# FPGA.net
KiCad netlist of a schematic drawn in Altium Designer
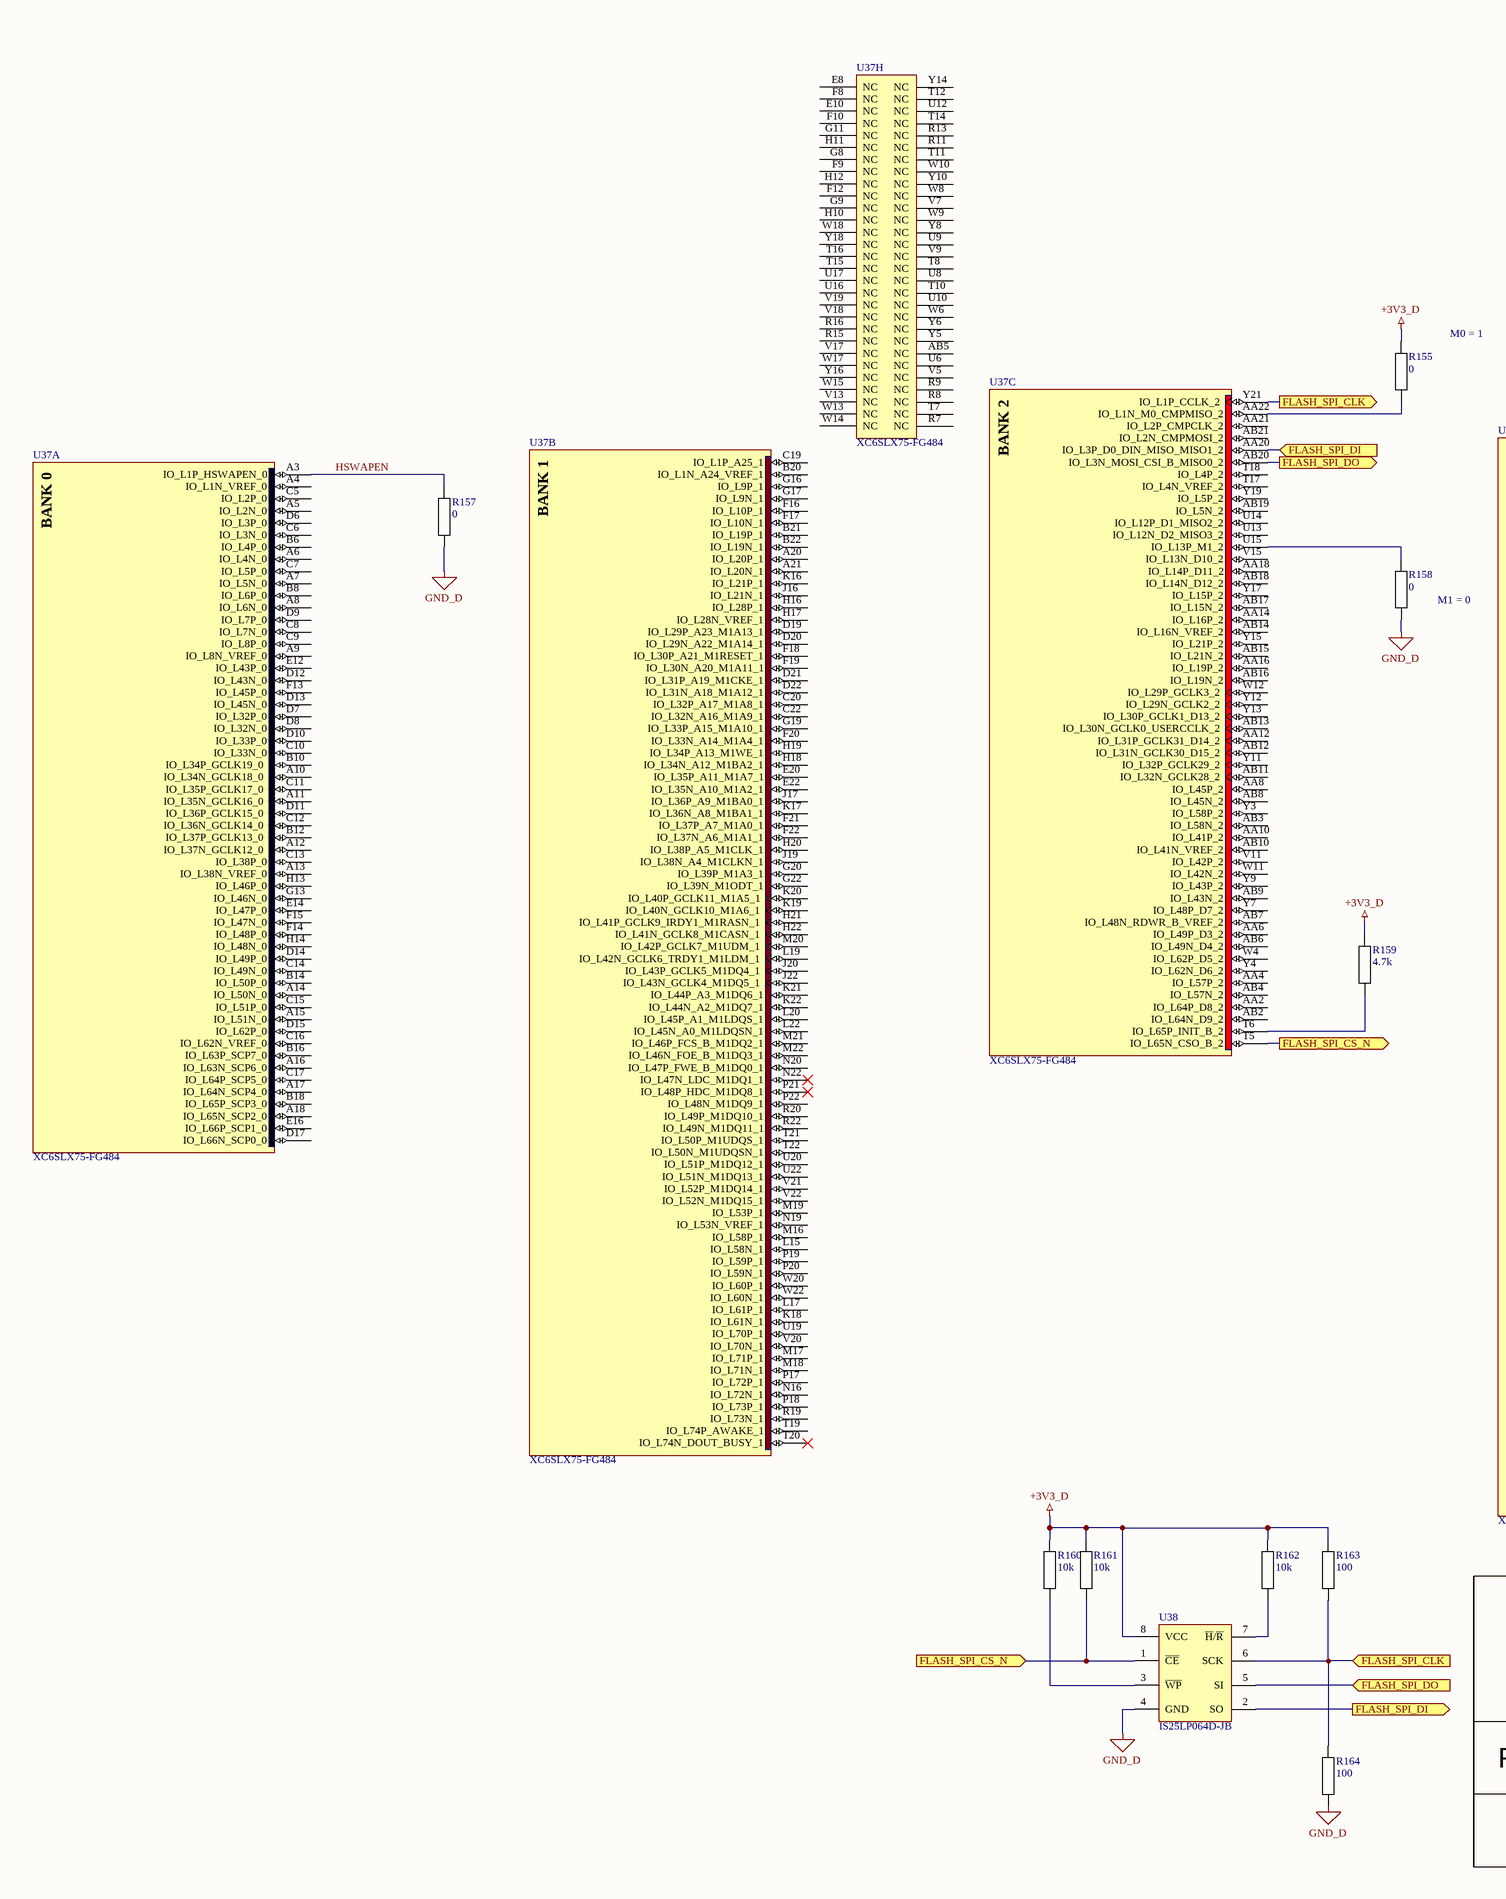
[diagram p0: FPGA.SchDoc, left]
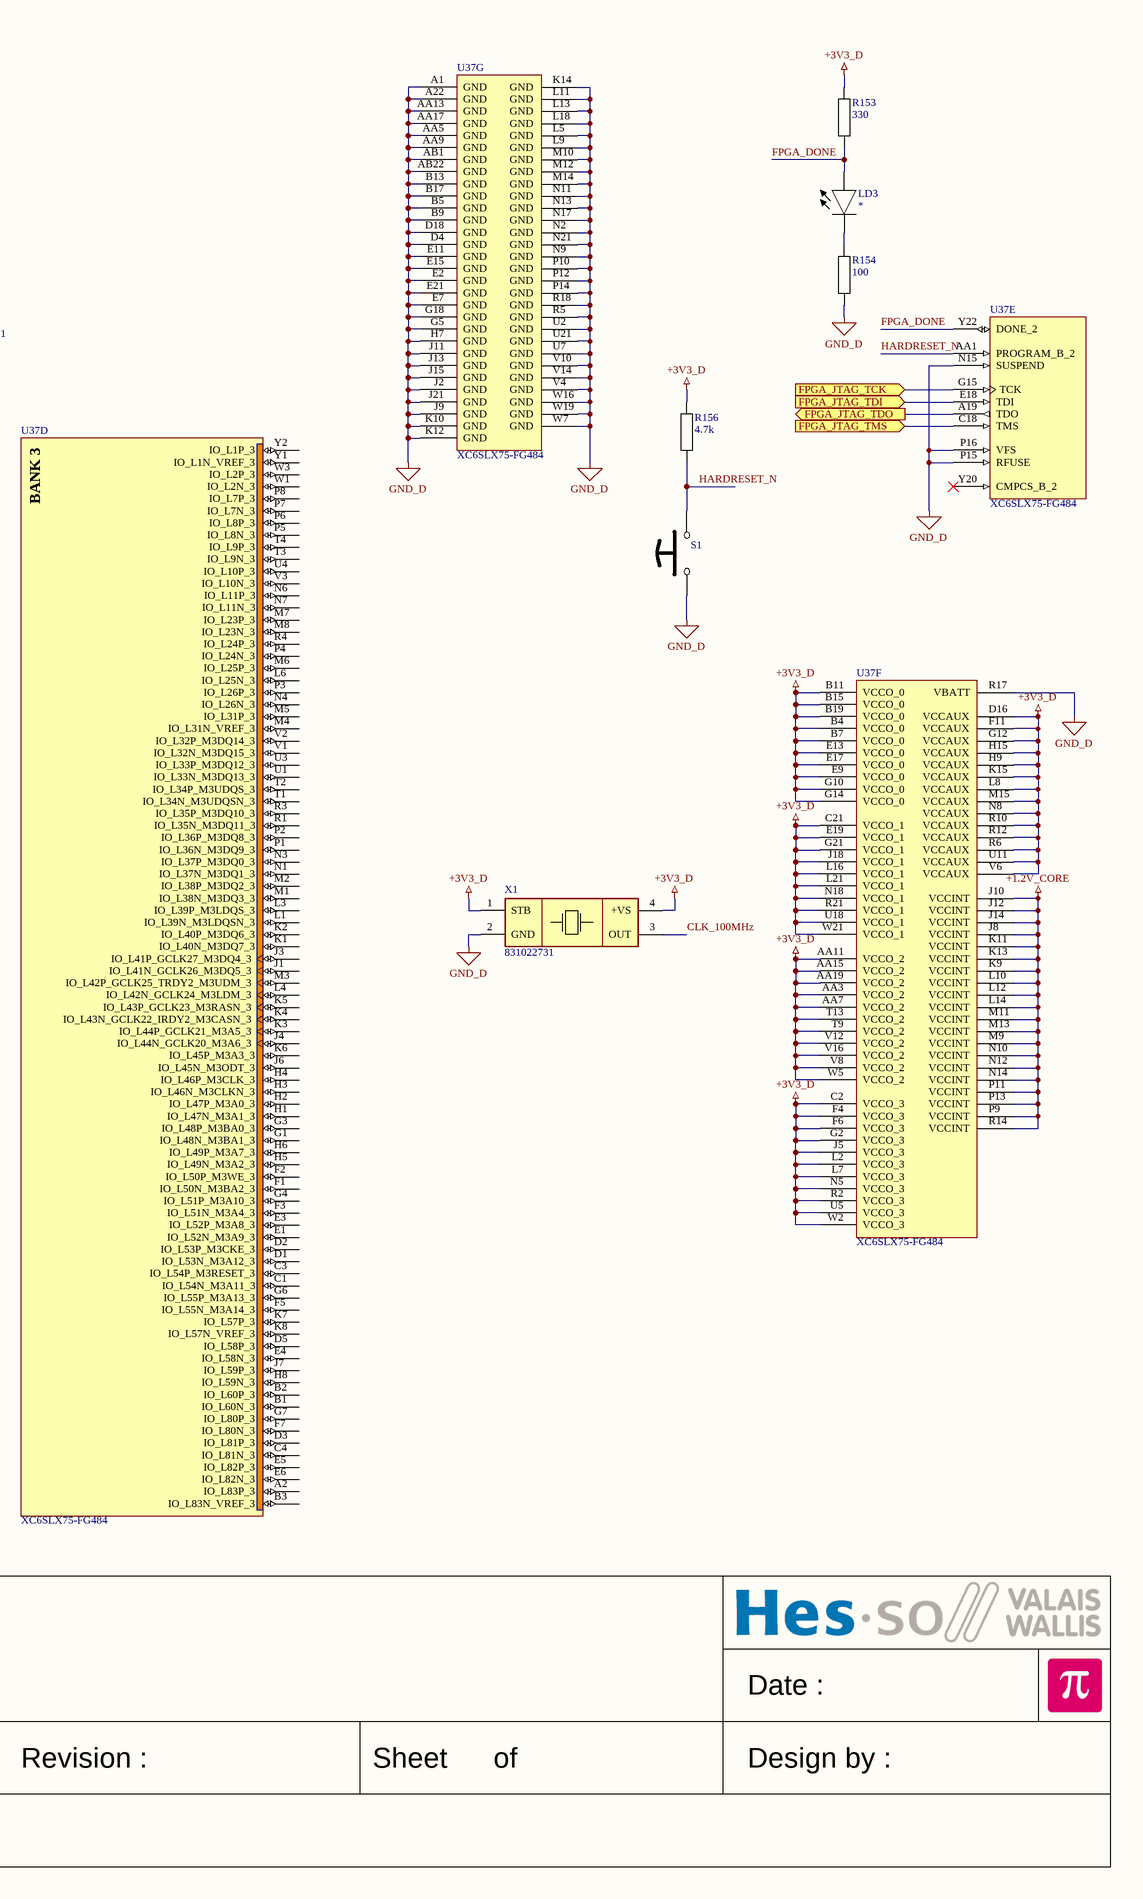
[diagram p1: FPGA.SchDoc, right]

(export (version "E")
  (design (tool "Eeschema 10.0.6"))
  (components
    (comp (ref "LD3")
      (value "*")
      (footprint "LED 1608 REFLOW")
      (description "LED generic")
      (libsource (lib "Diode") (part "LED"))
    )
    (comp (ref "R153")
      (value "330")
      (footprint "RESISTOR 2012 REFLOW")
      (description "Resistor 1% 50V 125mW 2012(0805)")
      (libsource (lib "Resistor") (part "Resistor"))
    )
    (comp (ref "R154")
      (value "100")
      (footprint "RESISTOR 2012 REFLOW")
      (description "Resistor 1% 50V 125mW 2012(0805)")
      (libsource (lib "Resistor") (part "Resistor"))
    )
    (comp (ref "R155")
      (value "0")
      (footprint "RESISTOR 2012 REFLOW")
      (description "Resistor 1% 50V 125mW 2012(0805)")
      (libsource (lib "Resistor") (part "Resistor"))
    )
    (comp (ref "R156")
      (value "4.7k")
      (footprint "RESISTOR 2012 REFLOW")
      (description "Resistor 1% 50V 125mW 2012(0805)")
      (libsource (lib "Resistor") (part "Resistor"))
    )
    (comp (ref "R157")
      (value "0")
      (footprint "RESISTOR 2012 REFLOW")
      (description "Resistor 1% 50V 125mW 2012(0805)")
      (libsource (lib "Resistor") (part "Resistor"))
    )
    (comp (ref "R158")
      (value "0")
      (footprint "RESISTOR 2012 REFLOW")
      (description "Resistor 1% 50V 125mW 2012(0805)")
      (libsource (lib "Resistor") (part "Resistor"))
    )
    (comp (ref "R159")
      (value "4.7k")
      (footprint "RESISTOR 2012 REFLOW")
      (description "Resistor 1% 50V 125mW 2012(0805)")
      (libsource (lib "Resistor") (part "Resistor"))
    )
    (comp (ref "R160")
      (value "10k")
      (footprint "RESISTOR 1608 REFLOW")
      (description "Resistor 1% 50V 100mW 1608(0603)")
      (libsource (lib "Resistor") (part "Resistor"))
    )
    (comp (ref "R161")
      (value "10k")
      (footprint "RESISTOR 1608 REFLOW")
      (description "Resistor 1% 50V 100mW 1608(0603)")
      (libsource (lib "Resistor") (part "Resistor"))
    )
    (comp (ref "R162")
      (value "10k")
      (footprint "RESISTOR 1608 REFLOW")
      (description "Resistor 1% 50V 100mW 1608(0603)")
      (libsource (lib "Resistor") (part "Resistor"))
    )
    (comp (ref "R163")
      (value "100")
      (footprint "RESISTOR 1608 REFLOW")
      (description "Resistor 1% 50V 100mW 1608(0603)")
      (libsource (lib "Resistor") (part "Resistor"))
    )
    (comp (ref "R164")
      (value "100")
      (footprint "RESISTOR 1608 REFLOW")
      (description "Resistor 1% 50V 100mW 1608(0603)")
      (libsource (lib "Resistor") (part "Resistor"))
    )
    (comp (ref "S1")
      (value "*")
      (footprint "Push Button C2.5X3.0 OMRON B3U-1000P(M)-B")
      (description "Push Button, 2 pins")
      (libsource (lib "Button") (part "Push Button 2Pins"))
    )
    (comp (ref "U37")
      (value "XC6SLX75-FG484")
      (footprint "BGA484 P1.0 C23X23 H2.2")
      (description "Spartan-6 LXT 1.2V FPGA, 268 User I/Os, 484-Ball Fine-Pitch BGA (1.0mm Pitch)")
      (libsource (lib "Processor") (part "XC6SLX75-FG484"))
    )
    (comp (ref "U38")
      (value "IS25LP064D-JB")
      (footprint "SO8 P1.27 C4.0X5.0 H1.75")
      (description "64Mb Serial Flash Memory")
      (libsource (lib "Memory") (part "IS25LP064D-JB"))
    )
    (comp (ref "X1")
      (value "831022731")
      (footprint "Oscillator C5.2x7.2 IQD LFSPXO")
      (description "Oscillator C5.2x7.2 IQD LFSPXO")
      (libsource (lib "Oscillator") (part "Oscillator C5.2x7.2 IQD LFSPXO"))
    )
  )
  (nets
    (net (code "1") (name "+1.2V_CORE") (class "Default")
      (node (ref "U37") (pin "J10") (pinfunction "VCCINT_J10") (pintype "power_in"))
      (node (ref "U37") (pin "J12") (pinfunction "VCCINT_J12") (pintype "power_in"))
      (node (ref "U37") (pin "J14") (pinfunction "VCCINT_J14") (pintype "power_in"))
      (node (ref "U37") (pin "J8") (pinfunction "VCCINT_J8") (pintype "power_in"))
      (node (ref "U37") (pin "K11") (pinfunction "VCCINT_K11") (pintype "power_in"))
      (node (ref "U37") (pin "K13") (pinfunction "VCCINT_K13") (pintype "power_in"))
      (node (ref "U37") (pin "K9") (pinfunction "VCCINT_K9") (pintype "power_in"))
      (node (ref "U37") (pin "L10") (pinfunction "VCCINT_L10") (pintype "power_in"))
      (node (ref "U37") (pin "L12") (pinfunction "VCCINT_L12") (pintype "power_in"))
      (node (ref "U37") (pin "L14") (pinfunction "VCCINT_L14") (pintype "power_in"))
      (node (ref "U37") (pin "M11") (pinfunction "VCCINT_M11") (pintype "power_in"))
      (node (ref "U37") (pin "M13") (pinfunction "VCCINT_M13") (pintype "power_in"))
      (node (ref "U37") (pin "M9") (pinfunction "VCCINT_M9") (pintype "power_in"))
      (node (ref "U37") (pin "N10") (pinfunction "VCCINT_N10") (pintype "power_in"))
      (node (ref "U37") (pin "N12") (pinfunction "VCCINT_N12") (pintype "power_in"))
      (node (ref "U37") (pin "N14") (pinfunction "VCCINT_N14") (pintype "power_in"))
      (node (ref "U37") (pin "P11") (pinfunction "VCCINT_P11") (pintype "power_in"))
      (node (ref "U37") (pin "P13") (pinfunction "VCCINT_P13") (pintype "power_in"))
      (node (ref "U37") (pin "P9") (pinfunction "VCCINT_P9") (pintype "power_in"))
      (node (ref "U37") (pin "R14") (pinfunction "VCCINT_R14") (pintype "power_in"))
    )
    (net (code "2") (name "+3V3_D") (class "Default")
      (node (ref "R153") (pin "2") (pinfunction "2_2") (pintype "passive"))
      (node (ref "R155") (pin "2") (pinfunction "2_2") (pintype "passive"))
      (node (ref "R156") (pin "2") (pinfunction "2_2") (pintype "passive"))
      (node (ref "R159") (pin "2") (pinfunction "2_2") (pintype "passive"))
      (node (ref "R160") (pin "2") (pinfunction "2_2") (pintype "passive"))
      (node (ref "R161") (pin "2") (pinfunction "2_2") (pintype "passive"))
      (node (ref "R162") (pin "2") (pinfunction "2_2") (pintype "passive"))
      (node (ref "R163") (pin "2") (pinfunction "2_2") (pintype "passive"))
      (node (ref "U37") (pin "AA11") (pinfunction "VCCO_2_AA11") (pintype "power_in"))
      (node (ref "U37") (pin "AA15") (pinfunction "VCCO_2_AA15") (pintype "power_in"))
      (node (ref "U37") (pin "AA19") (pinfunction "VCCO_2_AA19") (pintype "power_in"))
      (node (ref "U37") (pin "AA3") (pinfunction "VCCO_2_AA3") (pintype "power_in"))
      (node (ref "U37") (pin "AA7") (pinfunction "VCCO_2_AA7") (pintype "power_in"))
      (node (ref "U37") (pin "B11") (pinfunction "VCCO_0_B11") (pintype "power_in"))
      (node (ref "U37") (pin "B15") (pinfunction "VCCO_0_B15") (pintype "power_in"))
      (node (ref "U37") (pin "B19") (pinfunction "VCCO_0_B19") (pintype "power_in"))
      (node (ref "U37") (pin "B4") (pinfunction "VCCO_0_B4") (pintype "power_in"))
      (node (ref "U37") (pin "B7") (pinfunction "VCCO_0_B7") (pintype "power_in"))
      (node (ref "U37") (pin "C2") (pinfunction "VCCO_3_C2") (pintype "power_in"))
      (node (ref "U37") (pin "C21") (pinfunction "VCCO_1_C21") (pintype "power_in"))
      (node (ref "U37") (pin "D16") (pinfunction "VCCAUX_D16") (pintype "power_in"))
      (node (ref "U37") (pin "E13") (pinfunction "VCCO_0_E13") (pintype "power_in"))
      (node (ref "U37") (pin "E17") (pinfunction "VCCO_0_E17") (pintype "power_in"))
      (node (ref "U37") (pin "E19") (pinfunction "VCCO_1_E19") (pintype "power_in"))
      (node (ref "U37") (pin "E9") (pinfunction "VCCO_0_E9") (pintype "power_in"))
      (node (ref "U37") (pin "F11") (pinfunction "VCCAUX_F11") (pintype "power_in"))
      (node (ref "U37") (pin "F4") (pinfunction "VCCO_3_F4") (pintype "power_in"))
      (node (ref "U37") (pin "F6") (pinfunction "VCCO_3_F6") (pintype "power_in"))
      (node (ref "U37") (pin "G10") (pinfunction "VCCO_0_G10") (pintype "power_in"))
      (node (ref "U37") (pin "G12") (pinfunction "VCCAUX_G12") (pintype "power_in"))
      (node (ref "U37") (pin "G14") (pinfunction "VCCO_0_G14") (pintype "power_in"))
      (node (ref "U37") (pin "G2") (pinfunction "VCCO_3_G2") (pintype "power_in"))
      (node (ref "U37") (pin "G21") (pinfunction "VCCO_1_G21") (pintype "power_in"))
      (node (ref "U37") (pin "H15") (pinfunction "VCCAUX_H15") (pintype "power_in"))
      (node (ref "U37") (pin "H9") (pinfunction "VCCAUX_H9") (pintype "power_in"))
      (node (ref "U37") (pin "J18") (pinfunction "VCCO_1_J18") (pintype "power_in"))
      (node (ref "U37") (pin "J5") (pinfunction "VCCO_3_J5") (pintype "power_in"))
      (node (ref "U37") (pin "K15") (pinfunction "VCCAUX_K15") (pintype "power_in"))
      (node (ref "U37") (pin "L16") (pinfunction "VCCO_1_L16") (pintype "power_in"))
      (node (ref "U37") (pin "L2") (pinfunction "VCCO_3_L2") (pintype "power_in"))
      (node (ref "U37") (pin "L21") (pinfunction "VCCO_1_L21") (pintype "power_in"))
      (node (ref "U37") (pin "L7") (pinfunction "VCCO_3_L7") (pintype "power_in"))
      (node (ref "U37") (pin "L8") (pinfunction "VCCAUX_L8") (pintype "power_in"))
      (node (ref "U37") (pin "M15") (pinfunction "VCCAUX_M15") (pintype "power_in"))
      (node (ref "U37") (pin "N18") (pinfunction "VCCO_1_N18") (pintype "power_in"))
      (node (ref "U37") (pin "N5") (pinfunction "VCCO_3_N5") (pintype "power_in"))
      (node (ref "U37") (pin "N8") (pinfunction "VCCAUX_N8") (pintype "power_in"))
      (node (ref "U37") (pin "R10") (pinfunction "VCCAUX_R10") (pintype "power_in"))
      (node (ref "U37") (pin "R12") (pinfunction "VCCAUX_R12") (pintype "power_in"))
      (node (ref "U37") (pin "R2") (pinfunction "VCCO_3_R2") (pintype "power_in"))
      (node (ref "U37") (pin "R21") (pinfunction "VCCO_1_R21") (pintype "power_in"))
      (node (ref "U37") (pin "R6") (pinfunction "VCCAUX_R6") (pintype "power_in"))
      (node (ref "U37") (pin "T13") (pinfunction "VCCO_2_T13") (pintype "power_in"))
      (node (ref "U37") (pin "T9") (pinfunction "VCCO_2_T9") (pintype "power_in"))
      (node (ref "U37") (pin "U11") (pinfunction "VCCAUX_U11") (pintype "power_in"))
      (node (ref "U37") (pin "U18") (pinfunction "VCCO_1_U18") (pintype "power_in"))
      (node (ref "U37") (pin "U5") (pinfunction "VCCO_3_U5") (pintype "power_in"))
      (node (ref "U37") (pin "V12") (pinfunction "VCCO_2_V12") (pintype "power_in"))
      (node (ref "U37") (pin "V16") (pinfunction "VCCO_2_V16") (pintype "power_in"))
      (node (ref "U37") (pin "V6") (pinfunction "VCCAUX_V6") (pintype "power_in"))
      (node (ref "U37") (pin "V8") (pinfunction "VCCO_2_V8") (pintype "power_in"))
      (node (ref "U37") (pin "W2") (pinfunction "VCCO_3_W2") (pintype "power_in"))
      (node (ref "U37") (pin "W21") (pinfunction "VCCO_1_W21") (pintype "power_in"))
      (node (ref "U37") (pin "W5") (pinfunction "VCCO_2_W5") (pintype "power_in"))
      (node (ref "U38") (pin "8") (pinfunction "VCC_8") (pintype "power_in"))
      (node (ref "X1") (pin "1") (pinfunction "STB_1") (pintype "passive"))
      (node (ref "X1") (pin "4") (pinfunction "+VS_4") (pintype "passive"))
    )
    (net (code "3") (name "/CLK_100MHz") (class "Default")
      (node (ref "X1") (pin "3") (pinfunction "OUT_3") (pintype "passive"))
    )
    (net (code "4") (name "/FLASH_SPI_CLK") (class "Default")
      (node (ref "R163") (pin "1") (pinfunction "1_1") (pintype "passive"))
      (node (ref "R164") (pin "2") (pinfunction "2_2") (pintype "passive"))
      (node (ref "U37") (pin "Y21") (pinfunction "IO_L1P_CCLK_2_Y21") (pintype "bidirectional"))
      (node (ref "U38") (pin "6") (pinfunction "SCK_6") (pintype "passive"))
    )
    (net (code "5") (name "/FLASH_SPI_CS_N") (class "Default")
      (node (ref "R161") (pin "1") (pinfunction "1_1") (pintype "passive"))
      (node (ref "U37") (pin "T5") (pinfunction "IO_L65N_CSO_B_2_T5") (pintype "bidirectional"))
      (node (ref "U38") (pin "1") (pinfunction "~{CE}_1") (pintype "passive"))
    )
    (net (code "6") (name "/FLASH_SPI_DI") (class "Default")
      (node (ref "U37") (pin "AA20") (pinfunction "IO_L3P_D0_DIN_MISO_MISO1_2_AA20") (pintype "bidirectional"))
      (node (ref "U38") (pin "2") (pinfunction "SO_2") (pintype "passive"))
    )
    (net (code "7") (name "/FLASH_SPI_DO") (class "Default")
      (node (ref "U37") (pin "AB20") (pinfunction "IO_L3N_MOSI_CSI_B_MISO0_2_AB20") (pintype "bidirectional"))
      (node (ref "U38") (pin "5") (pinfunction "SI_5") (pintype "passive"))
    )
    (net (code "8") (name "/FPGA_DONE") (class "Default")
      (node (ref "LD3") (pin "2") (pinfunction "A_2") (pintype "passive"))
      (node (ref "R153") (pin "1") (pinfunction "1_1") (pintype "passive"))
      (node (ref "U37") (pin "Y22") (pinfunction "DONE_2_Y22") (pintype "bidirectional"))
    )
    (net (code "9") (name "/FPGA_JTAG_TCK") (class "Default")
      (node (ref "U37") (pin "G15") (pinfunction "TCK_G15") (pintype "input"))
    )
    (net (code "10") (name "/FPGA_JTAG_TDI") (class "Default")
      (node (ref "U37") (pin "E18") (pinfunction "TDI_E18") (pintype "input"))
    )
    (net (code "11") (name "/FPGA_JTAG_TDO") (class "Default")
      (node (ref "U37") (pin "A19") (pinfunction "TDO_A19") (pintype "output"))
    )
    (net (code "12") (name "/FPGA_JTAG_TMS") (class "Default")
      (node (ref "U37") (pin "C18") (pinfunction "TMS_C18") (pintype "input"))
    )
    (net (code "13") (name "/HARDRESET_N") (class "Default")
      (node (ref "R156") (pin "1") (pinfunction "1_1") (pintype "passive"))
      (node (ref "S1") (pin "2") (pinfunction "2_2") (pintype "passive"))
      (node (ref "U37") (pin "AA1") (pinfunction "PROGRAM_B_2_AA1") (pintype "input"))
    )
    (net (code "14") (name "/HSWAPEN") (class "Default")
      (node (ref "R157") (pin "2") (pinfunction "2_2") (pintype "passive"))
      (node (ref "U37") (pin "A3") (pinfunction "IO_L1P_HSWAPEN_0_A3") (pintype "bidirectional"))
    )
    (net (code "15") (name "GND_D") (class "Default")
      (node (ref "R154") (pin "1") (pinfunction "1_1") (pintype "passive"))
      (node (ref "R157") (pin "1") (pinfunction "1_1") (pintype "passive"))
      (node (ref "R158") (pin "1") (pinfunction "1_1") (pintype "passive"))
      (node (ref "R164") (pin "1") (pinfunction "1_1") (pintype "passive"))
      (node (ref "S1") (pin "1") (pinfunction "1_1") (pintype "passive"))
      (node (ref "U37") (pin "A1") (pinfunction "GND_A1") (pintype "power_in"))
      (node (ref "U37") (pin "A22") (pinfunction "GND_A22") (pintype "power_in"))
      (node (ref "U37") (pin "AA13") (pinfunction "GND_AA13") (pintype "power_in"))
      (node (ref "U37") (pin "AA17") (pinfunction "GND_AA17") (pintype "power_in"))
      (node (ref "U37") (pin "AA5") (pinfunction "GND_AA5") (pintype "power_in"))
      (node (ref "U37") (pin "AA9") (pinfunction "GND_AA9") (pintype "power_in"))
      (node (ref "U37") (pin "AB1") (pinfunction "GND_AB1") (pintype "power_in"))
      (node (ref "U37") (pin "AB22") (pinfunction "GND_AB22") (pintype "power_in"))
      (node (ref "U37") (pin "B13") (pinfunction "GND_B13") (pintype "power_in"))
      (node (ref "U37") (pin "B17") (pinfunction "GND_B17") (pintype "power_in"))
      (node (ref "U37") (pin "B5") (pinfunction "GND_B5") (pintype "power_in"))
      (node (ref "U37") (pin "B9") (pinfunction "GND_B9") (pintype "power_in"))
      (node (ref "U37") (pin "D18") (pinfunction "GND_D18") (pintype "power_in"))
      (node (ref "U37") (pin "D4") (pinfunction "GND_D4") (pintype "power_in"))
      (node (ref "U37") (pin "E11") (pinfunction "GND_E11") (pintype "power_in"))
      (node (ref "U37") (pin "E15") (pinfunction "GND_E15") (pintype "power_in"))
      (node (ref "U37") (pin "E2") (pinfunction "GND_E2") (pintype "power_in"))
      (node (ref "U37") (pin "E21") (pinfunction "GND_E21") (pintype "power_in"))
      (node (ref "U37") (pin "E7") (pinfunction "GND_E7") (pintype "power_in"))
      (node (ref "U37") (pin "G18") (pinfunction "GND_G18") (pintype "power_in"))
      (node (ref "U37") (pin "G5") (pinfunction "GND_G5") (pintype "power_in"))
      (node (ref "U37") (pin "H7") (pinfunction "GND_H7") (pintype "power_in"))
      (node (ref "U37") (pin "J11") (pinfunction "GND_J11") (pintype "power_in"))
      (node (ref "U37") (pin "J13") (pinfunction "GND_J13") (pintype "power_in"))
      (node (ref "U37") (pin "J15") (pinfunction "GND_J15") (pintype "power_in"))
      (node (ref "U37") (pin "J2") (pinfunction "GND_J2") (pintype "power_in"))
      (node (ref "U37") (pin "J21") (pinfunction "GND_J21") (pintype "power_in"))
      (node (ref "U37") (pin "J9") (pinfunction "GND_J9") (pintype "power_in"))
      (node (ref "U37") (pin "K10") (pinfunction "GND_K10") (pintype "power_in"))
      (node (ref "U37") (pin "K12") (pinfunction "GND_K12") (pintype "power_in"))
      (node (ref "U37") (pin "K14") (pinfunction "GND_K14") (pintype "power_in"))
      (node (ref "U37") (pin "L11") (pinfunction "GND_L11") (pintype "power_in"))
      (node (ref "U37") (pin "L13") (pinfunction "GND_L13") (pintype "power_in"))
      (node (ref "U37") (pin "L18") (pinfunction "GND_L18") (pintype "power_in"))
      (node (ref "U37") (pin "L5") (pinfunction "GND_L5") (pintype "power_in"))
      (node (ref "U37") (pin "L9") (pinfunction "GND_L9") (pintype "power_in"))
      (node (ref "U37") (pin "M10") (pinfunction "GND_M10") (pintype "power_in"))
      (node (ref "U37") (pin "M12") (pinfunction "GND_M12") (pintype "power_in"))
      (node (ref "U37") (pin "M14") (pinfunction "GND_M14") (pintype "power_in"))
      (node (ref "U37") (pin "N11") (pinfunction "GND_N11") (pintype "power_in"))
      (node (ref "U37") (pin "N13") (pinfunction "GND_N13") (pintype "power_in"))
      (node (ref "U37") (pin "N15") (pinfunction "SUSPEND_N15") (pintype "input"))
      (node (ref "U37") (pin "N17") (pinfunction "GND_N17") (pintype "power_in"))
      (node (ref "U37") (pin "N2") (pinfunction "GND_N2") (pintype "power_in"))
      (node (ref "U37") (pin "N21") (pinfunction "GND_N21") (pintype "power_in"))
      (node (ref "U37") (pin "N9") (pinfunction "GND_N9") (pintype "power_in"))
      (node (ref "U37") (pin "P10") (pinfunction "GND_P10") (pintype "power_in"))
      (node (ref "U37") (pin "P12") (pinfunction "GND_P12") (pintype "power_in"))
      (node (ref "U37") (pin "P14") (pinfunction "GND_P14") (pintype "power_in"))
      (node (ref "U37") (pin "P15") (pinfunction "RFUSE_P15") (pintype "input"))
      (node (ref "U37") (pin "P16") (pinfunction "VFS_P16") (pintype "input"))
      (node (ref "U37") (pin "R17") (pinfunction "VBATT_R17") (pintype "power_in"))
      (node (ref "U37") (pin "R18") (pinfunction "GND_R18") (pintype "power_in"))
      (node (ref "U37") (pin "R5") (pinfunction "GND_R5") (pintype "power_in"))
      (node (ref "U37") (pin "U2") (pinfunction "GND_U2") (pintype "power_in"))
      (node (ref "U37") (pin "U21") (pinfunction "GND_U21") (pintype "power_in"))
      (node (ref "U37") (pin "U7") (pinfunction "GND_U7") (pintype "power_in"))
      (node (ref "U37") (pin "V10") (pinfunction "GND_V10") (pintype "power_in"))
      (node (ref "U37") (pin "V14") (pinfunction "GND_V14") (pintype "power_in"))
      (node (ref "U37") (pin "V4") (pinfunction "GND_V4") (pintype "power_in"))
      (node (ref "U37") (pin "W16") (pinfunction "GND_W16") (pintype "power_in"))
      (node (ref "U37") (pin "W19") (pinfunction "GND_W19") (pintype "power_in"))
      (node (ref "U37") (pin "W7") (pinfunction "GND_W7") (pintype "power_in"))
      (node (ref "U38") (pin "4") (pinfunction "GND_4") (pintype "power_in"))
      (node (ref "X1") (pin "2") (pinfunction "GND_2") (pintype "passive"))
    )
    (net (code "16") (name "Net-(LD3-C)") (class "Default")
      (node (ref "LD3") (pin "1") (pinfunction "C_1") (pintype "passive"))
      (node (ref "R154") (pin "2") (pinfunction "2_2") (pintype "passive"))
    )
    (net (code "17") (name "Net-(U37C-IO_L1N_M0_CMPMISO_2)") (class "Default")
      (node (ref "R155") (pin "1") (pinfunction "1_1") (pintype "passive"))
      (node (ref "U37") (pin "AA22") (pinfunction "IO_L1N_M0_CMPMISO_2_AA22") (pintype "bidirectional"))
    )
    (net (code "18") (name "Net-(U37C-IO_L13P_M1_2)") (class "Default")
      (node (ref "R158") (pin "2") (pinfunction "2_2") (pintype "passive"))
      (node (ref "U37") (pin "U15") (pinfunction "IO_L13P_M1_2_U15") (pintype "bidirectional"))
    )
    (net (code "19") (name "Net-(U37C-IO_L65P_INIT_B_2)") (class "Default")
      (node (ref "R159") (pin "1") (pinfunction "1_1") (pintype "passive"))
      (node (ref "U37") (pin "T6") (pinfunction "IO_L65P_INIT_B_2_T6") (pintype "bidirectional"))
    )
    (net (code "20") (name "Net-(U38-~{H}{slash}~{R})") (class "Default")
      (node (ref "R162") (pin "1") (pinfunction "1_1") (pintype "passive"))
      (node (ref "U38") (pin "7") (pinfunction "~{H}/~{R}_7") (pintype "passive"))
    )
    (net (code "21") (name "Net-(U38-~{WP})") (class "Default")
      (node (ref "R160") (pin "1") (pinfunction "1_1") (pintype "passive"))
      (node (ref "U38") (pin "3") (pinfunction "~{WP}_3") (pintype "passive"))
    )
    (net (code "22") (name "unconnected-(U37A-IO_L1N_VREF_0-PadA4)") (class "Default")
      (node (ref "U37") (pin "A4") (pinfunction "IO_L1N_VREF_0_A4") (pintype "bidirectional"))
    )
    (net (code "23") (name "unconnected-(U37A-IO_L2N_0-PadA5)") (class "Default")
      (node (ref "U37") (pin "A5") (pinfunction "IO_L2N_0_A5") (pintype "bidirectional"))
    )
    (net (code "24") (name "unconnected-(U37A-IO_L2P_0-PadC5)") (class "Default")
      (node (ref "U37") (pin "C5") (pinfunction "IO_L2P_0_C5") (pintype "bidirectional"))
    )
    (net (code "25") (name "unconnected-(U37A-IO_L3N_0-PadC6)") (class "Default")
      (node (ref "U37") (pin "C6") (pinfunction "IO_L3N_0_C6") (pintype "bidirectional"))
    )
    (net (code "26") (name "unconnected-(U37A-IO_L3P_0-PadD6)") (class "Default")
      (node (ref "U37") (pin "D6") (pinfunction "IO_L3P_0_D6") (pintype "bidirectional"))
    )
    (net (code "27") (name "unconnected-(U37A-IO_L4N_0-PadA6)") (class "Default")
      (node (ref "U37") (pin "A6") (pinfunction "IO_L4N_0_A6") (pintype "bidirectional"))
    )
    (net (code "28") (name "unconnected-(U37A-IO_L4P_0-PadB6)") (class "Default")
      (node (ref "U37") (pin "B6") (pinfunction "IO_L4P_0_B6") (pintype "bidirectional"))
    )
    (net (code "29") (name "unconnected-(U37A-IO_L5N_0-PadA7)") (class "Default")
      (node (ref "U37") (pin "A7") (pinfunction "IO_L5N_0_A7") (pintype "bidirectional"))
    )
    (net (code "30") (name "unconnected-(U37A-IO_L5P_0-PadC7)") (class "Default")
      (node (ref "U37") (pin "C7") (pinfunction "IO_L5P_0_C7") (pintype "bidirectional"))
    )
    (net (code "31") (name "unconnected-(U37A-IO_L6N_0-PadA8)") (class "Default")
      (node (ref "U37") (pin "A8") (pinfunction "IO_L6N_0_A8") (pintype "bidirectional"))
    )
    (net (code "32") (name "unconnected-(U37A-IO_L6P_0-PadB8)") (class "Default")
      (node (ref "U37") (pin "B8") (pinfunction "IO_L6P_0_B8") (pintype "bidirectional"))
    )
    (net (code "33") (name "unconnected-(U37A-IO_L7N_0-PadC8)") (class "Default")
      (node (ref "U37") (pin "C8") (pinfunction "IO_L7N_0_C8") (pintype "bidirectional"))
    )
    (net (code "34") (name "unconnected-(U37A-IO_L7P_0-PadD9)") (class "Default")
      (node (ref "U37") (pin "D9") (pinfunction "IO_L7P_0_D9") (pintype "bidirectional"))
    )
    (net (code "35") (name "unconnected-(U37A-IO_L8N_VREF_0-PadA9)") (class "Default")
      (node (ref "U37") (pin "A9") (pinfunction "IO_L8N_VREF_0_A9") (pintype "bidirectional"))
    )
    (net (code "36") (name "unconnected-(U37A-IO_L8P_0-PadC9)") (class "Default")
      (node (ref "U37") (pin "C9") (pinfunction "IO_L8P_0_C9") (pintype "bidirectional"))
    )
    (net (code "37") (name "unconnected-(U37A-IO_L32N_0-PadD8)") (class "Default")
      (node (ref "U37") (pin "D8") (pinfunction "IO_L32N_0_D8") (pintype "bidirectional"))
    )
    (net (code "38") (name "unconnected-(U37A-IO_L32P_0-PadD7)") (class "Default")
      (node (ref "U37") (pin "D7") (pinfunction "IO_L32P_0_D7") (pintype "bidirectional"))
    )
    (net (code "39") (name "unconnected-(U37A-IO_L33N_0-PadC10)") (class "Default")
      (node (ref "U37") (pin "C10") (pinfunction "IO_L33N_0_C10") (pintype "bidirectional"))
    )
    (net (code "40") (name "unconnected-(U37A-IO_L33P_0-PadD10)") (class "Default")
      (node (ref "U37") (pin "D10") (pinfunction "IO_L33P_0_D10") (pintype "bidirectional"))
    )
    (net (code "41") (name "unconnected-(U37A-IO_L34N_GCLK18_0-PadA10)") (class "Default")
      (node (ref "U37") (pin "A10") (pinfunction "IO_L34N_GCLK18_0_A10") (pintype "bidirectional"))
    )
    (net (code "42") (name "unconnected-(U37A-IO_L34P_GCLK19_0-PadB10)") (class "Default")
      (node (ref "U37") (pin "B10") (pinfunction "IO_L34P_GCLK19_0_B10") (pintype "bidirectional"))
    )
    (net (code "43") (name "unconnected-(U37A-IO_L35N_GCLK16_0-PadA11)") (class "Default")
      (node (ref "U37") (pin "A11") (pinfunction "IO_L35N_GCLK16_0_A11") (pintype "bidirectional"))
    )
    (net (code "44") (name "unconnected-(U37A-IO_L35P_GCLK17_0-PadC11)") (class "Default")
      (node (ref "U37") (pin "C11") (pinfunction "IO_L35P_GCLK17_0_C11") (pintype "bidirectional"))
    )
    (net (code "45") (name "unconnected-(U37A-IO_L36N_GCLK14_0-PadC12)") (class "Default")
      (node (ref "U37") (pin "C12") (pinfunction "IO_L36N_GCLK14_0_C12") (pintype "bidirectional"))
    )
    (net (code "46") (name "unconnected-(U37A-IO_L36P_GCLK15_0-PadD11)") (class "Default")
      (node (ref "U37") (pin "D11") (pinfunction "IO_L36P_GCLK15_0_D11") (pintype "bidirectional"))
    )
    (net (code "47") (name "unconnected-(U37A-IO_L37N_GCLK12_0-PadA12)") (class "Default")
      (node (ref "U37") (pin "A12") (pinfunction "IO_L37N_GCLK12_0_A12") (pintype "bidirectional"))
    )
    (net (code "48") (name "unconnected-(U37A-IO_L37P_GCLK13_0-PadB12)") (class "Default")
      (node (ref "U37") (pin "B12") (pinfunction "IO_L37P_GCLK13_0_B12") (pintype "bidirectional"))
    )
    (net (code "49") (name "unconnected-(U37A-IO_L38N_VREF_0-PadA13)") (class "Default")
      (node (ref "U37") (pin "A13") (pinfunction "IO_L38N_VREF_0_A13") (pintype "bidirectional"))
    )
    (net (code "50") (name "unconnected-(U37A-IO_L38P_0-PadC13)") (class "Default")
      (node (ref "U37") (pin "C13") (pinfunction "IO_L38P_0_C13") (pintype "bidirectional"))
    )
    (net (code "51") (name "unconnected-(U37A-IO_L43N_0-PadD12)") (class "Default")
      (node (ref "U37") (pin "D12") (pinfunction "IO_L43N_0_D12") (pintype "bidirectional"))
    )
    (net (code "52") (name "unconnected-(U37A-IO_L43P_0-PadE12)") (class "Default")
      (node (ref "U37") (pin "E12") (pinfunction "IO_L43P_0_E12") (pintype "bidirectional"))
    )
    (net (code "53") (name "unconnected-(U37A-IO_L45N_0-PadD13)") (class "Default")
      (node (ref "U37") (pin "D13") (pinfunction "IO_L45N_0_D13") (pintype "bidirectional"))
    )
    (net (code "54") (name "unconnected-(U37A-IO_L45P_0-PadF13)") (class "Default")
      (node (ref "U37") (pin "F13") (pinfunction "IO_L45P_0_F13") (pintype "bidirectional"))
    )
    (net (code "55") (name "unconnected-(U37A-IO_L46N_0-PadG13)") (class "Default")
      (node (ref "U37") (pin "G13") (pinfunction "IO_L46N_0_G13") (pintype "bidirectional"))
    )
    (net (code "56") (name "unconnected-(U37A-IO_L46P_0-PadH13)") (class "Default")
      (node (ref "U37") (pin "H13") (pinfunction "IO_L46P_0_H13") (pintype "bidirectional"))
    )
    (net (code "57") (name "unconnected-(U37A-IO_L47N_0-PadF15)") (class "Default")
      (node (ref "U37") (pin "F15") (pinfunction "IO_L47N_0_F15") (pintype "bidirectional"))
    )
    (net (code "58") (name "unconnected-(U37A-IO_L47P_0-PadE14)") (class "Default")
      (node (ref "U37") (pin "E14") (pinfunction "IO_L47P_0_E14") (pintype "bidirectional"))
    )
    (net (code "59") (name "unconnected-(U37A-IO_L48N_0-PadH14)") (class "Default")
      (node (ref "U37") (pin "H14") (pinfunction "IO_L48N_0_H14") (pintype "bidirectional"))
    )
    (net (code "60") (name "unconnected-(U37A-IO_L48P_0-PadF14)") (class "Default")
      (node (ref "U37") (pin "F14") (pinfunction "IO_L48P_0_F14") (pintype "bidirectional"))
    )
    (net (code "61") (name "unconnected-(U37A-IO_L49N_0-PadC14)") (class "Default")
      (node (ref "U37") (pin "C14") (pinfunction "IO_L49N_0_C14") (pintype "bidirectional"))
    )
    (net (code "62") (name "unconnected-(U37A-IO_L49P_0-PadD14)") (class "Default")
      (node (ref "U37") (pin "D14") (pinfunction "IO_L49P_0_D14") (pintype "bidirectional"))
    )
    (net (code "63") (name "unconnected-(U37A-IO_L50N_0-PadA14)") (class "Default")
      (node (ref "U37") (pin "A14") (pinfunction "IO_L50N_0_A14") (pintype "bidirectional"))
    )
    (net (code "64") (name "unconnected-(U37A-IO_L50P_0-PadB14)") (class "Default")
      (node (ref "U37") (pin "B14") (pinfunction "IO_L50P_0_B14") (pintype "bidirectional"))
    )
    (net (code "65") (name "unconnected-(U37A-IO_L51N_0-PadA15)") (class "Default")
      (node (ref "U37") (pin "A15") (pinfunction "IO_L51N_0_A15") (pintype "bidirectional"))
    )
    (net (code "66") (name "unconnected-(U37A-IO_L51P_0-PadC15)") (class "Default")
      (node (ref "U37") (pin "C15") (pinfunction "IO_L51P_0_C15") (pintype "bidirectional"))
    )
    (net (code "67") (name "unconnected-(U37A-IO_L62N_VREF_0-PadC16)") (class "Default")
      (node (ref "U37") (pin "C16") (pinfunction "IO_L62N_VREF_0_C16") (pintype "bidirectional"))
    )
    (net (code "68") (name "unconnected-(U37A-IO_L62P_0-PadD15)") (class "Default")
      (node (ref "U37") (pin "D15") (pinfunction "IO_L62P_0_D15") (pintype "bidirectional"))
    )
    (net (code "69") (name "unconnected-(U37A-IO_L63N_SCP6_0-PadA16)") (class "Default")
      (node (ref "U37") (pin "A16") (pinfunction "IO_L63N_SCP6_0_A16") (pintype "bidirectional"))
    )
    (net (code "70") (name "unconnected-(U37A-IO_L63P_SCP7_0-PadB16)") (class "Default")
      (node (ref "U37") (pin "B16") (pinfunction "IO_L63P_SCP7_0_B16") (pintype "bidirectional"))
    )
    (net (code "71") (name "unconnected-(U37A-IO_L64N_SCP4_0-PadA17)") (class "Default")
      (node (ref "U37") (pin "A17") (pinfunction "IO_L64N_SCP4_0_A17") (pintype "bidirectional"))
    )
    (net (code "72") (name "unconnected-(U37A-IO_L64P_SCP5_0-PadC17)") (class "Default")
      (node (ref "U37") (pin "C17") (pinfunction "IO_L64P_SCP5_0_C17") (pintype "bidirectional"))
    )
    (net (code "73") (name "unconnected-(U37A-IO_L65N_SCP2_0-PadA18)") (class "Default")
      (node (ref "U37") (pin "A18") (pinfunction "IO_L65N_SCP2_0_A18") (pintype "bidirectional"))
    )
    (net (code "74") (name "unconnected-(U37A-IO_L65P_SCP3_0-PadB18)") (class "Default")
      (node (ref "U37") (pin "B18") (pinfunction "IO_L65P_SCP3_0_B18") (pintype "bidirectional"))
    )
    (net (code "75") (name "unconnected-(U37A-IO_L66N_SCP0_0-PadD17)") (class "Default")
      (node (ref "U37") (pin "D17") (pinfunction "IO_L66N_SCP0_0_D17") (pintype "bidirectional"))
    )
    (net (code "76") (name "unconnected-(U37A-IO_L66P_SCP1_0-PadE16)") (class "Default")
      (node (ref "U37") (pin "E16") (pinfunction "IO_L66P_SCP1_0_E16") (pintype "bidirectional"))
    )
    (net (code "77") (name "unconnected-(U37B-IO_L1N_A24_VREF_1-PadB20)") (class "Default")
      (node (ref "U37") (pin "B20") (pinfunction "IO_L1N_A24_VREF_1_B20") (pintype "bidirectional"))
    )
    (net (code "78") (name "unconnected-(U37B-IO_L1P_A25_1-PadC19)") (class "Default")
      (node (ref "U37") (pin "C19") (pinfunction "IO_L1P_A25_1_C19") (pintype "bidirectional"))
    )
    (net (code "79") (name "unconnected-(U37B-IO_L9N_1-PadG17)") (class "Default")
      (node (ref "U37") (pin "G17") (pinfunction "IO_L9N_1_G17") (pintype "bidirectional"))
    )
    (net (code "80") (name "unconnected-(U37B-IO_L9P_1-PadG16)") (class "Default")
      (node (ref "U37") (pin "G16") (pinfunction "IO_L9P_1_G16") (pintype "bidirectional"))
    )
    (net (code "81") (name "unconnected-(U37B-IO_L10N_1-PadF17)") (class "Default")
      (node (ref "U37") (pin "F17") (pinfunction "IO_L10N_1_F17") (pintype "bidirectional"))
    )
    (net (code "82") (name "unconnected-(U37B-IO_L10P_1-PadF16)") (class "Default")
      (node (ref "U37") (pin "F16") (pinfunction "IO_L10P_1_F16") (pintype "bidirectional"))
    )
    (net (code "83") (name "unconnected-(U37B-IO_L19N_1-PadB22)") (class "Default")
      (node (ref "U37") (pin "B22") (pinfunction "IO_L19N_1_B22") (pintype "bidirectional"))
    )
    (net (code "84") (name "unconnected-(U37B-IO_L19P_1-PadB21)") (class "Default")
      (node (ref "U37") (pin "B21") (pinfunction "IO_L19P_1_B21") (pintype "bidirectional"))
    )
    (net (code "85") (name "unconnected-(U37B-IO_L20N_1-PadA21)") (class "Default")
      (node (ref "U37") (pin "A21") (pinfunction "IO_L20N_1_A21") (pintype "bidirectional"))
    )
    (net (code "86") (name "unconnected-(U37B-IO_L20P_1-PadA20)") (class "Default")
      (node (ref "U37") (pin "A20") (pinfunction "IO_L20P_1_A20") (pintype "bidirectional"))
    )
    (net (code "87") (name "unconnected-(U37B-IO_L21N_1-PadJ16)") (class "Default")
      (node (ref "U37") (pin "J16") (pinfunction "IO_L21N_1_J16") (pintype "bidirectional"))
    )
    (net (code "88") (name "unconnected-(U37B-IO_L21P_1-PadK16)") (class "Default")
      (node (ref "U37") (pin "K16") (pinfunction "IO_L21P_1_K16") (pintype "bidirectional"))
    )
    (net (code "89") (name "unconnected-(U37B-IO_L28N_VREF_1-PadH17)") (class "Default")
      (node (ref "U37") (pin "H17") (pinfunction "IO_L28N_VREF_1_H17") (pintype "bidirectional"))
    )
    (net (code "90") (name "unconnected-(U37B-IO_L28P_1-PadH16)") (class "Default")
      (node (ref "U37") (pin "H16") (pinfunction "IO_L28P_1_H16") (pintype "bidirectional"))
    )
    (net (code "91") (name "unconnected-(U37B-IO_L29N_A22_M1A14_1-PadD20)") (class "Default")
      (node (ref "U37") (pin "D20") (pinfunction "IO_L29N_A22_M1A14_1_D20") (pintype "bidirectional"))
    )
    (net (code "92") (name "unconnected-(U37B-IO_L29P_A23_M1A13_1-PadD19)") (class "Default")
      (node (ref "U37") (pin "D19") (pinfunction "IO_L29P_A23_M1A13_1_D19") (pintype "bidirectional"))
    )
    (net (code "93") (name "unconnected-(U37B-IO_L30N_A20_M1A11_1-PadF19)") (class "Default")
      (node (ref "U37") (pin "F19") (pinfunction "IO_L30N_A20_M1A11_1_F19") (pintype "bidirectional"))
    )
    (net (code "94") (name "unconnected-(U37B-IO_L30P_A21_M1RESET_1-PadF18)") (class "Default")
      (node (ref "U37") (pin "F18") (pinfunction "IO_L30P_A21_M1RESET_1_F18") (pintype "bidirectional"))
    )
    (net (code "95") (name "unconnected-(U37B-IO_L31N_A18_M1A12_1-PadD22)") (class "Default")
      (node (ref "U37") (pin "D22") (pinfunction "IO_L31N_A18_M1A12_1_D22") (pintype "bidirectional"))
    )
    (net (code "96") (name "unconnected-(U37B-IO_L31P_A19_M1CKE_1-PadD21)") (class "Default")
      (node (ref "U37") (pin "D21") (pinfunction "IO_L31P_A19_M1CKE_1_D21") (pintype "bidirectional"))
    )
    (net (code "97") (name "unconnected-(U37B-IO_L32N_A16_M1A9_1-PadC22)") (class "Default")
      (node (ref "U37") (pin "C22") (pinfunction "IO_L32N_A16_M1A9_1_C22") (pintype "bidirectional"))
    )
    (net (code "98") (name "unconnected-(U37B-IO_L32P_A17_M1A8_1-PadC20)") (class "Default")
      (node (ref "U37") (pin "C20") (pinfunction "IO_L32P_A17_M1A8_1_C20") (pintype "bidirectional"))
    )
    (net (code "99") (name "unconnected-(U37B-IO_L33N_A14_M1A4_1-PadF20)") (class "Default")
      (node (ref "U37") (pin "F20") (pinfunction "IO_L33N_A14_M1A4_1_F20") (pintype "bidirectional"))
    )
    (net (code "100") (name "unconnected-(U37B-IO_L33P_A15_M1A10_1-PadG19)") (class "Default")
      (node (ref "U37") (pin "G19") (pinfunction "IO_L33P_A15_M1A10_1_G19") (pintype "bidirectional"))
    )
    (net (code "101") (name "unconnected-(U37B-IO_L34N_A12_M1BA2_1-PadH18)") (class "Default")
      (node (ref "U37") (pin "H18") (pinfunction "IO_L34N_A12_M1BA2_1_H18") (pintype "bidirectional"))
    )
    (net (code "102") (name "unconnected-(U37B-IO_L34P_A13_M1WE_1-PadH19)") (class "Default")
      (node (ref "U37") (pin "H19") (pinfunction "IO_L34P_A13_M1WE_1_H19") (pintype "bidirectional"))
    )
    (net (code "103") (name "unconnected-(U37B-IO_L35N_A10_M1A2_1-PadE22)") (class "Default")
      (node (ref "U37") (pin "E22") (pinfunction "IO_L35N_A10_M1A2_1_E22") (pintype "bidirectional"))
    )
    (net (code "104") (name "unconnected-(U37B-IO_L35P_A11_M1A7_1-PadE20)") (class "Default")
      (node (ref "U37") (pin "E20") (pinfunction "IO_L35P_A11_M1A7_1_E20") (pintype "bidirectional"))
    )
    (net (code "105") (name "unconnected-(U37B-IO_L36N_A8_M1BA1_1-PadK17)") (class "Default")
      (node (ref "U37") (pin "K17") (pinfunction "IO_L36N_A8_M1BA1_1_K17") (pintype "bidirectional"))
    )
    (net (code "106") (name "unconnected-(U37B-IO_L36P_A9_M1BA0_1-PadJ17)") (class "Default")
      (node (ref "U37") (pin "J17") (pinfunction "IO_L36P_A9_M1BA0_1_J17") (pintype "bidirectional"))
    )
    (net (code "107") (name "unconnected-(U37B-IO_L37N_A6_M1A1_1-PadF22)") (class "Default")
      (node (ref "U37") (pin "F22") (pinfunction "IO_L37N_A6_M1A1_1_F22") (pintype "bidirectional"))
    )
    (net (code "108") (name "unconnected-(U37B-IO_L37P_A7_M1A0_1-PadF21)") (class "Default")
      (node (ref "U37") (pin "F21") (pinfunction "IO_L37P_A7_M1A0_1_F21") (pintype "bidirectional"))
    )
    (net (code "109") (name "unconnected-(U37B-IO_L38N_A4_M1CLKN_1-PadJ19)") (class "Default")
      (node (ref "U37") (pin "J19") (pinfunction "IO_L38N_A4_M1CLKN_1_J19") (pintype "bidirectional"))
    )
    (net (code "110") (name "unconnected-(U37B-IO_L38P_A5_M1CLK_1-PadH20)") (class "Default")
      (node (ref "U37") (pin "H20") (pinfunction "IO_L38P_A5_M1CLK_1_H20") (pintype "bidirectional"))
    )
    (net (code "111") (name "unconnected-(U37B-IO_L39N_M1ODT_1-PadG22)") (class "Default")
      (node (ref "U37") (pin "G22") (pinfunction "IO_L39N_M1ODT_1_G22") (pintype "bidirectional"))
    )
    (net (code "112") (name "unconnected-(U37B-IO_L39P_M1A3_1-PadG20)") (class "Default")
      (node (ref "U37") (pin "G20") (pinfunction "IO_L39P_M1A3_1_G20") (pintype "bidirectional"))
    )
    (net (code "113") (name "unconnected-(U37B-IO_L40N_GCLK10_M1A6_1-PadK19)") (class "Default")
      (node (ref "U37") (pin "K19") (pinfunction "IO_L40N_GCLK10_M1A6_1_K19") (pintype "bidirectional"))
    )
    (net (code "114") (name "unconnected-(U37B-IO_L40P_GCLK11_M1A5_1-PadK20)") (class "Default")
      (node (ref "U37") (pin "K20") (pinfunction "IO_L40P_GCLK11_M1A5_1_K20") (pintype "bidirectional"))
    )
    (net (code "115") (name "unconnected-(U37B-IO_L41N_GCLK8_M1CASN_1-PadH22)") (class "Default")
      (node (ref "U37") (pin "H22") (pinfunction "IO_L41N_GCLK8_M1CASN_1_H22") (pintype "bidirectional"))
    )
    (net (code "116") (name "unconnected-(U37B-IO_L41P_GCLK9_IRDY1_M1RASN_1-PadH21)") (class "Default")
      (node (ref "U37") (pin "H21") (pinfunction "IO_L41P_GCLK9_IRDY1_M1RASN_1_H21") (pintype "bidirectional"))
    )
    (net (code "117") (name "unconnected-(U37B-IO_L42N_GCLK6_TRDY1_M1LDM_1-PadL19)") (class "Default")
      (node (ref "U37") (pin "L19") (pinfunction "IO_L42N_GCLK6_TRDY1_M1LDM_1_L19") (pintype "bidirectional"))
    )
    (net (code "118") (name "unconnected-(U37B-IO_L42P_GCLK7_M1UDM_1-PadM20)") (class "Default")
      (node (ref "U37") (pin "M20") (pinfunction "IO_L42P_GCLK7_M1UDM_1_M20") (pintype "bidirectional"))
    )
    (net (code "119") (name "unconnected-(U37B-IO_L43N_GCLK4_M1DQ5_1-PadJ22)") (class "Default")
      (node (ref "U37") (pin "J22") (pinfunction "IO_L43N_GCLK4_M1DQ5_1_J22") (pintype "bidirectional"))
    )
    (net (code "120") (name "unconnected-(U37B-IO_L43P_GCLK5_M1DQ4_1-PadJ20)") (class "Default")
      (node (ref "U37") (pin "J20") (pinfunction "IO_L43P_GCLK5_M1DQ4_1_J20") (pintype "bidirectional"))
    )
    (net (code "121") (name "unconnected-(U37B-IO_L44N_A2_M1DQ7_1-PadK22)") (class "Default")
      (node (ref "U37") (pin "K22") (pinfunction "IO_L44N_A2_M1DQ7_1_K22") (pintype "bidirectional"))
    )
    (net (code "122") (name "unconnected-(U37B-IO_L44P_A3_M1DQ6_1-PadK21)") (class "Default")
      (node (ref "U37") (pin "K21") (pinfunction "IO_L44P_A3_M1DQ6_1_K21") (pintype "bidirectional"))
    )
    (net (code "123") (name "unconnected-(U37B-IO_L45N_A0_M1LDQSN_1-PadL22)") (class "Default")
      (node (ref "U37") (pin "L22") (pinfunction "IO_L45N_A0_M1LDQSN_1_L22") (pintype "bidirectional"))
    )
    (net (code "124") (name "unconnected-(U37B-IO_L45P_A1_M1LDQS_1-PadL20)") (class "Default")
      (node (ref "U37") (pin "L20") (pinfunction "IO_L45P_A1_M1LDQS_1_L20") (pintype "bidirectional"))
    )
    (net (code "125") (name "unconnected-(U37B-IO_L46N_FOE_B_M1DQ3_1-PadM22)") (class "Default")
      (node (ref "U37") (pin "M22") (pinfunction "IO_L46N_FOE_B_M1DQ3_1_M22") (pintype "bidirectional"))
    )
    (net (code "126") (name "unconnected-(U37B-IO_L46P_FCS_B_M1DQ2_1-PadM21)") (class "Default")
      (node (ref "U37") (pin "M21") (pinfunction "IO_L46P_FCS_B_M1DQ2_1_M21") (pintype "bidirectional"))
    )
    (net (code "127") (name "unconnected-(U37B-IO_L47N_LDC_M1DQ1_1-PadN22)") (class "Default")
      (node (ref "U37") (pin "N22") (pinfunction "IO_L47N_LDC_M1DQ1_1_N22") (pintype "bidirectional+no_connect"))
    )
    (net (code "128") (name "unconnected-(U37B-IO_L47P_FWE_B_M1DQ0_1-PadN20)") (class "Default")
      (node (ref "U37") (pin "N20") (pinfunction "IO_L47P_FWE_B_M1DQ0_1_N20") (pintype "bidirectional"))
    )
    (net (code "129") (name "unconnected-(U37B-IO_L48N_M1DQ9_1-PadP22)") (class "Default")
      (node (ref "U37") (pin "P22") (pinfunction "IO_L48N_M1DQ9_1_P22") (pintype "bidirectional"))
    )
    (net (code "130") (name "unconnected-(U37B-IO_L48P_HDC_M1DQ8_1-PadP21)") (class "Default")
      (node (ref "U37") (pin "P21") (pinfunction "IO_L48P_HDC_M1DQ8_1_P21") (pintype "bidirectional+no_connect"))
    )
    (net (code "131") (name "unconnected-(U37B-IO_L49N_M1DQ11_1-PadR22)") (class "Default")
      (node (ref "U37") (pin "R22") (pinfunction "IO_L49N_M1DQ11_1_R22") (pintype "bidirectional"))
    )
    (net (code "132") (name "unconnected-(U37B-IO_L49P_M1DQ10_1-PadR20)") (class "Default")
      (node (ref "U37") (pin "R20") (pinfunction "IO_L49P_M1DQ10_1_R20") (pintype "bidirectional"))
    )
    (net (code "133") (name "unconnected-(U37B-IO_L50N_M1UDQSN_1-PadT22)") (class "Default")
      (node (ref "U37") (pin "T22") (pinfunction "IO_L50N_M1UDQSN_1_T22") (pintype "bidirectional"))
    )
    (net (code "134") (name "unconnected-(U37B-IO_L50P_M1UDQS_1-PadT21)") (class "Default")
      (node (ref "U37") (pin "T21") (pinfunction "IO_L50P_M1UDQS_1_T21") (pintype "bidirectional"))
    )
    (net (code "135") (name "unconnected-(U37B-IO_L51N_M1DQ13_1-PadU22)") (class "Default")
      (node (ref "U37") (pin "U22") (pinfunction "IO_L51N_M1DQ13_1_U22") (pintype "bidirectional"))
    )
    (net (code "136") (name "unconnected-(U37B-IO_L51P_M1DQ12_1-PadU20)") (class "Default")
      (node (ref "U37") (pin "U20") (pinfunction "IO_L51P_M1DQ12_1_U20") (pintype "bidirectional"))
    )
    (net (code "137") (name "unconnected-(U37B-IO_L52N_M1DQ15_1-PadV22)") (class "Default")
      (node (ref "U37") (pin "V22") (pinfunction "IO_L52N_M1DQ15_1_V22") (pintype "bidirectional"))
    )
    (net (code "138") (name "unconnected-(U37B-IO_L52P_M1DQ14_1-PadV21)") (class "Default")
      (node (ref "U37") (pin "V21") (pinfunction "IO_L52P_M1DQ14_1_V21") (pintype "bidirectional"))
    )
    (net (code "139") (name "unconnected-(U37B-IO_L53N_VREF_1-PadN19)") (class "Default")
      (node (ref "U37") (pin "N19") (pinfunction "IO_L53N_VREF_1_N19") (pintype "bidirectional"))
    )
    (net (code "140") (name "unconnected-(U37B-IO_L53P_1-PadM19)") (class "Default")
      (node (ref "U37") (pin "M19") (pinfunction "IO_L53P_1_M19") (pintype "bidirectional"))
    )
    (net (code "141") (name "unconnected-(U37B-IO_L58N_1-PadL15)") (class "Default")
      (node (ref "U37") (pin "L15") (pinfunction "IO_L58N_1_L15") (pintype "bidirectional"))
    )
    (net (code "142") (name "unconnected-(U37B-IO_L58P_1-PadM16)") (class "Default")
      (node (ref "U37") (pin "M16") (pinfunction "IO_L58P_1_M16") (pintype "bidirectional"))
    )
    (net (code "143") (name "unconnected-(U37B-IO_L59N_1-PadP20)") (class "Default")
      (node (ref "U37") (pin "P20") (pinfunction "IO_L59N_1_P20") (pintype "bidirectional"))
    )
    (net (code "144") (name "unconnected-(U37B-IO_L59P_1-PadP19)") (class "Default")
      (node (ref "U37") (pin "P19") (pinfunction "IO_L59P_1_P19") (pintype "bidirectional"))
    )
    (net (code "145") (name "unconnected-(U37B-IO_L60N_1-PadW22)") (class "Default")
      (node (ref "U37") (pin "W22") (pinfunction "IO_L60N_1_W22") (pintype "bidirectional"))
    )
    (net (code "146") (name "unconnected-(U37B-IO_L60P_1-PadW20)") (class "Default")
      (node (ref "U37") (pin "W20") (pinfunction "IO_L60P_1_W20") (pintype "bidirectional"))
    )
    (net (code "147") (name "unconnected-(U37B-IO_L61N_1-PadK18)") (class "Default")
      (node (ref "U37") (pin "K18") (pinfunction "IO_L61N_1_K18") (pintype "bidirectional"))
    )
    (net (code "148") (name "unconnected-(U37B-IO_L61P_1-PadL17)") (class "Default")
      (node (ref "U37") (pin "L17") (pinfunction "IO_L61P_1_L17") (pintype "bidirectional"))
    )
    (net (code "149") (name "unconnected-(U37B-IO_L70N_1-PadV20)") (class "Default")
      (node (ref "U37") (pin "V20") (pinfunction "IO_L70N_1_V20") (pintype "bidirectional"))
    )
    (net (code "150") (name "unconnected-(U37B-IO_L70P_1-PadU19)") (class "Default")
      (node (ref "U37") (pin "U19") (pinfunction "IO_L70P_1_U19") (pintype "bidirectional"))
    )
    (net (code "151") (name "unconnected-(U37B-IO_L71N_1-PadM18)") (class "Default")
      (node (ref "U37") (pin "M18") (pinfunction "IO_L71N_1_M18") (pintype "bidirectional"))
    )
    (net (code "152") (name "unconnected-(U37B-IO_L71P_1-PadM17)") (class "Default")
      (node (ref "U37") (pin "M17") (pinfunction "IO_L71P_1_M17") (pintype "bidirectional"))
    )
    (net (code "153") (name "unconnected-(U37B-IO_L72N_1-PadN16)") (class "Default")
      (node (ref "U37") (pin "N16") (pinfunction "IO_L72N_1_N16") (pintype "bidirectional"))
    )
    (net (code "154") (name "unconnected-(U37B-IO_L72P_1-PadP17)") (class "Default")
      (node (ref "U37") (pin "P17") (pinfunction "IO_L72P_1_P17") (pintype "bidirectional"))
    )
    (net (code "155") (name "unconnected-(U37B-IO_L73N_1-PadR19)") (class "Default")
      (node (ref "U37") (pin "R19") (pinfunction "IO_L73N_1_R19") (pintype "bidirectional"))
    )
    (net (code "156") (name "unconnected-(U37B-IO_L73P_1-PadP18)") (class "Default")
      (node (ref "U37") (pin "P18") (pinfunction "IO_L73P_1_P18") (pintype "bidirectional"))
    )
    (net (code "157") (name "unconnected-(U37B-IO_L74N_DOUT_BUSY_1-PadT20)") (class "Default")
      (node (ref "U37") (pin "T20") (pinfunction "IO_L74N_DOUT_BUSY_1_T20") (pintype "bidirectional+no_connect"))
    )
    (net (code "158") (name "unconnected-(U37B-IO_L74P_AWAKE_1-PadT19)") (class "Default")
      (node (ref "U37") (pin "T19") (pinfunction "IO_L74P_AWAKE_1_T19") (pintype "bidirectional"))
    )
    (net (code "159") (name "unconnected-(U37C-IO_L2N_CMPMOSI_2-PadAB21)") (class "Default")
      (node (ref "U37") (pin "AB21") (pinfunction "IO_L2N_CMPMOSI_2_AB21") (pintype "bidirectional"))
    )
    (net (code "160") (name "unconnected-(U37C-IO_L2P_CMPCLK_2-PadAA21)") (class "Default")
      (node (ref "U37") (pin "AA21") (pinfunction "IO_L2P_CMPCLK_2_AA21") (pintype "bidirectional"))
    )
    (net (code "161") (name "unconnected-(U37C-IO_L4N_VREF_2-PadT17)") (class "Default")
      (node (ref "U37") (pin "T17") (pinfunction "IO_L4N_VREF_2_T17") (pintype "bidirectional"))
    )
    (net (code "162") (name "unconnected-(U37C-IO_L4P_2-PadT18)") (class "Default")
      (node (ref "U37") (pin "T18") (pinfunction "IO_L4P_2_T18") (pintype "bidirectional"))
    )
    (net (code "163") (name "unconnected-(U37C-IO_L5N_2-PadAB19)") (class "Default")
      (node (ref "U37") (pin "AB19") (pinfunction "IO_L5N_2_AB19") (pintype "bidirectional"))
    )
    (net (code "164") (name "unconnected-(U37C-IO_L5P_2-PadY19)") (class "Default")
      (node (ref "U37") (pin "Y19") (pinfunction "IO_L5P_2_Y19") (pintype "bidirectional"))
    )
    (net (code "165") (name "unconnected-(U37C-IO_L12N_D2_MISO3_2-PadU13)") (class "Default")
      (node (ref "U37") (pin "U13") (pinfunction "IO_L12N_D2_MISO3_2_U13") (pintype "bidirectional"))
    )
    (net (code "166") (name "unconnected-(U37C-IO_L12P_D1_MISO2_2-PadU14)") (class "Default")
      (node (ref "U37") (pin "U14") (pinfunction "IO_L12P_D1_MISO2_2_U14") (pintype "bidirectional"))
    )
    (net (code "167") (name "unconnected-(U37C-IO_L13N_D10_2-PadV15)") (class "Default")
      (node (ref "U37") (pin "V15") (pinfunction "IO_L13N_D10_2_V15") (pintype "bidirectional"))
    )
    (net (code "168") (name "unconnected-(U37C-IO_L14N_D12_2-PadAB18)") (class "Default")
      (node (ref "U37") (pin "AB18") (pinfunction "IO_L14N_D12_2_AB18") (pintype "bidirectional"))
    )
    (net (code "169") (name "unconnected-(U37C-IO_L14P_D11_2-PadAA18)") (class "Default")
      (node (ref "U37") (pin "AA18") (pinfunction "IO_L14P_D11_2_AA18") (pintype "bidirectional"))
    )
    (net (code "170") (name "unconnected-(U37C-IO_L15N_2-PadAB17)") (class "Default")
      (node (ref "U37") (pin "AB17") (pinfunction "IO_L15N_2_AB17") (pintype "bidirectional"))
    )
    (net (code "171") (name "unconnected-(U37C-IO_L15P_2-PadY17)") (class "Default")
      (node (ref "U37") (pin "Y17") (pinfunction "IO_L15P_2_Y17") (pintype "bidirectional"))
    )
    (net (code "172") (name "unconnected-(U37C-IO_L16N_VREF_2-PadAB14)") (class "Default")
      (node (ref "U37") (pin "AB14") (pinfunction "IO_L16N_VREF_2_AB14") (pintype "bidirectional"))
    )
    (net (code "173") (name "unconnected-(U37C-IO_L16P_2-PadAA14)") (class "Default")
      (node (ref "U37") (pin "AA14") (pinfunction "IO_L16P_2_AA14") (pintype "bidirectional"))
    )
    (net (code "174") (name "unconnected-(U37C-IO_L19N_2-PadAB16)") (class "Default")
      (node (ref "U37") (pin "AB16") (pinfunction "IO_L19N_2_AB16") (pintype "bidirectional"))
    )
    (net (code "175") (name "unconnected-(U37C-IO_L19P_2-PadAA16)") (class "Default")
      (node (ref "U37") (pin "AA16") (pinfunction "IO_L19P_2_AA16") (pintype "bidirectional"))
    )
    (net (code "176") (name "unconnected-(U37C-IO_L21N_2-PadAB15)") (class "Default")
      (node (ref "U37") (pin "AB15") (pinfunction "IO_L21N_2_AB15") (pintype "bidirectional"))
    )
    (net (code "177") (name "unconnected-(U37C-IO_L21P_2-PadY15)") (class "Default")
      (node (ref "U37") (pin "Y15") (pinfunction "IO_L21P_2_Y15") (pintype "bidirectional"))
    )
    (net (code "178") (name "unconnected-(U37C-IO_L29N_GCLK2_2-PadY12)") (class "Default")
      (node (ref "U37") (pin "Y12") (pinfunction "IO_L29N_GCLK2_2_Y12") (pintype "bidirectional"))
    )
    (net (code "179") (name "unconnected-(U37C-IO_L29P_GCLK3_2-PadW12)") (class "Default")
      (node (ref "U37") (pin "W12") (pinfunction "IO_L29P_GCLK3_2_W12") (pintype "bidirectional"))
    )
    (net (code "180") (name "unconnected-(U37C-IO_L30N_GCLK0_USERCCLK_2-PadAB13)") (class "Default")
      (node (ref "U37") (pin "AB13") (pinfunction "IO_L30N_GCLK0_USERCCLK_2_AB13") (pintype "bidirectional"))
    )
    (net (code "181") (name "unconnected-(U37C-IO_L30P_GCLK1_D13_2-PadY13)") (class "Default")
      (node (ref "U37") (pin "Y13") (pinfunction "IO_L30P_GCLK1_D13_2_Y13") (pintype "bidirectional"))
    )
    (net (code "182") (name "unconnected-(U37C-IO_L31N_GCLK30_D15_2-PadAB12)") (class "Default")
      (node (ref "U37") (pin "AB12") (pinfunction "IO_L31N_GCLK30_D15_2_AB12") (pintype "bidirectional"))
    )
    (net (code "183") (name "unconnected-(U37C-IO_L31P_GCLK31_D14_2-PadAA12)") (class "Default")
      (node (ref "U37") (pin "AA12") (pinfunction "IO_L31P_GCLK31_D14_2_AA12") (pintype "bidirectional"))
    )
    (net (code "184") (name "unconnected-(U37C-IO_L32N_GCLK28_2-PadAB11)") (class "Default")
      (node (ref "U37") (pin "AB11") (pinfunction "IO_L32N_GCLK28_2_AB11") (pintype "bidirectional"))
    )
    (net (code "185") (name "unconnected-(U37C-IO_L32P_GCLK29_2-PadY11)") (class "Default")
      (node (ref "U37") (pin "Y11") (pinfunction "IO_L32P_GCLK29_2_Y11") (pintype "bidirectional"))
    )
    (net (code "186") (name "unconnected-(U37C-IO_L41N_VREF_2-PadAB10)") (class "Default")
      (node (ref "U37") (pin "AB10") (pinfunction "IO_L41N_VREF_2_AB10") (pintype "bidirectional"))
    )
    (net (code "187") (name "unconnected-(U37C-IO_L41P_2-PadAA10)") (class "Default")
      (node (ref "U37") (pin "AA10") (pinfunction "IO_L41P_2_AA10") (pintype "bidirectional"))
    )
    (net (code "188") (name "unconnected-(U37C-IO_L42N_2-PadW11)") (class "Default")
      (node (ref "U37") (pin "W11") (pinfunction "IO_L42N_2_W11") (pintype "bidirectional"))
    )
    (net (code "189") (name "unconnected-(U37C-IO_L42P_2-PadV11)") (class "Default")
      (node (ref "U37") (pin "V11") (pinfunction "IO_L42P_2_V11") (pintype "bidirectional"))
    )
    (net (code "190") (name "unconnected-(U37C-IO_L43N_2-PadAB9)") (class "Default")
      (node (ref "U37") (pin "AB9") (pinfunction "IO_L43N_2_AB9") (pintype "bidirectional"))
    )
    (net (code "191") (name "unconnected-(U37C-IO_L43P_2-PadY9)") (class "Default")
      (node (ref "U37") (pin "Y9") (pinfunction "IO_L43P_2_Y9") (pintype "bidirectional"))
    )
    (net (code "192") (name "unconnected-(U37C-IO_L45N_2-PadAB8)") (class "Default")
      (node (ref "U37") (pin "AB8") (pinfunction "IO_L45N_2_AB8") (pintype "bidirectional"))
    )
    (net (code "193") (name "unconnected-(U37C-IO_L45P_2-PadAA8)") (class "Default")
      (node (ref "U37") (pin "AA8") (pinfunction "IO_L45P_2_AA8") (pintype "bidirectional"))
    )
    (net (code "194") (name "unconnected-(U37C-IO_L48N_RDWR_B_VREF_2-PadAB7)") (class "Default")
      (node (ref "U37") (pin "AB7") (pinfunction "IO_L48N_RDWR_B_VREF_2_AB7") (pintype "bidirectional"))
    )
    (net (code "195") (name "unconnected-(U37C-IO_L48P_D7_2-PadY7)") (class "Default")
      (node (ref "U37") (pin "Y7") (pinfunction "IO_L48P_D7_2_Y7") (pintype "bidirectional"))
    )
    (net (code "196") (name "unconnected-(U37C-IO_L49N_D4_2-PadAB6)") (class "Default")
      (node (ref "U37") (pin "AB6") (pinfunction "IO_L49N_D4_2_AB6") (pintype "bidirectional"))
    )
    (net (code "197") (name "unconnected-(U37C-IO_L49P_D3_2-PadAA6)") (class "Default")
      (node (ref "U37") (pin "AA6") (pinfunction "IO_L49P_D3_2_AA6") (pintype "bidirectional"))
    )
    (net (code "198") (name "unconnected-(U37C-IO_L57N_2-PadAB4)") (class "Default")
      (node (ref "U37") (pin "AB4") (pinfunction "IO_L57N_2_AB4") (pintype "bidirectional"))
    )
    (net (code "199") (name "unconnected-(U37C-IO_L57P_2-PadAA4)") (class "Default")
      (node (ref "U37") (pin "AA4") (pinfunction "IO_L57P_2_AA4") (pintype "bidirectional"))
    )
    (net (code "200") (name "unconnected-(U37C-IO_L58N_2-PadAB3)") (class "Default")
      (node (ref "U37") (pin "AB3") (pinfunction "IO_L58N_2_AB3") (pintype "bidirectional"))
    )
    (net (code "201") (name "unconnected-(U37C-IO_L58P_2-PadY3)") (class "Default")
      (node (ref "U37") (pin "Y3") (pinfunction "IO_L58P_2_Y3") (pintype "bidirectional"))
    )
    (net (code "202") (name "unconnected-(U37C-IO_L62N_D6_2-PadY4)") (class "Default")
      (node (ref "U37") (pin "Y4") (pinfunction "IO_L62N_D6_2_Y4") (pintype "bidirectional"))
    )
    (net (code "203") (name "unconnected-(U37C-IO_L62P_D5_2-PadW4)") (class "Default")
      (node (ref "U37") (pin "W4") (pinfunction "IO_L62P_D5_2_W4") (pintype "bidirectional"))
    )
    (net (code "204") (name "unconnected-(U37C-IO_L64N_D9_2-PadAB2)") (class "Default")
      (node (ref "U37") (pin "AB2") (pinfunction "IO_L64N_D9_2_AB2") (pintype "bidirectional"))
    )
    (net (code "205") (name "unconnected-(U37C-IO_L64P_D8_2-PadAA2)") (class "Default")
      (node (ref "U37") (pin "AA2") (pinfunction "IO_L64P_D8_2_AA2") (pintype "bidirectional"))
    )
    (net (code "206") (name "unconnected-(U37D-IO_L1N_VREF_3-PadY1)") (class "Default")
      (node (ref "U37") (pin "Y1") (pinfunction "IO_L1N_VREF_3_Y1") (pintype "bidirectional"))
    )
    (net (code "207") (name "unconnected-(U37D-IO_L1P_3-PadY2)") (class "Default")
      (node (ref "U37") (pin "Y2") (pinfunction "IO_L1P_3_Y2") (pintype "bidirectional"))
    )
    (net (code "208") (name "unconnected-(U37D-IO_L2N_3-PadW1)") (class "Default")
      (node (ref "U37") (pin "W1") (pinfunction "IO_L2N_3_W1") (pintype "bidirectional"))
    )
    (net (code "209") (name "unconnected-(U37D-IO_L2P_3-PadW3)") (class "Default")
      (node (ref "U37") (pin "W3") (pinfunction "IO_L2P_3_W3") (pintype "bidirectional"))
    )
    (net (code "210") (name "unconnected-(U37D-IO_L7N_3-PadP7)") (class "Default")
      (node (ref "U37") (pin "P7") (pinfunction "IO_L7N_3_P7") (pintype "bidirectional"))
    )
    (net (code "211") (name "unconnected-(U37D-IO_L7P_3-PadP8)") (class "Default")
      (node (ref "U37") (pin "P8") (pinfunction "IO_L7P_3_P8") (pintype "bidirectional"))
    )
    (net (code "212") (name "unconnected-(U37D-IO_L8N_3-PadP5)") (class "Default")
      (node (ref "U37") (pin "P5") (pinfunction "IO_L8N_3_P5") (pintype "bidirectional"))
    )
    (net (code "213") (name "unconnected-(U37D-IO_L8P_3-PadP6)") (class "Default")
      (node (ref "U37") (pin "P6") (pinfunction "IO_L8P_3_P6") (pintype "bidirectional"))
    )
    (net (code "214") (name "unconnected-(U37D-IO_L9N_3-PadT3)") (class "Default")
      (node (ref "U37") (pin "T3") (pinfunction "IO_L9N_3_T3") (pintype "bidirectional"))
    )
    (net (code "215") (name "unconnected-(U37D-IO_L9P_3-PadT4)") (class "Default")
      (node (ref "U37") (pin "T4") (pinfunction "IO_L9P_3_T4") (pintype "bidirectional"))
    )
    (net (code "216") (name "unconnected-(U37D-IO_L10N_3-PadV3)") (class "Default")
      (node (ref "U37") (pin "V3") (pinfunction "IO_L10N_3_V3") (pintype "bidirectional"))
    )
    (net (code "217") (name "unconnected-(U37D-IO_L10P_3-PadU4)") (class "Default")
      (node (ref "U37") (pin "U4") (pinfunction "IO_L10P_3_U4") (pintype "bidirectional"))
    )
    (net (code "218") (name "unconnected-(U37D-IO_L11N_3-PadN7)") (class "Default")
      (node (ref "U37") (pin "N7") (pinfunction "IO_L11N_3_N7") (pintype "bidirectional"))
    )
    (net (code "219") (name "unconnected-(U37D-IO_L11P_3-PadN6)") (class "Default")
      (node (ref "U37") (pin "N6") (pinfunction "IO_L11P_3_N6") (pintype "bidirectional"))
    )
    (net (code "220") (name "unconnected-(U37D-IO_L23N_3-PadM8)") (class "Default")
      (node (ref "U37") (pin "M8") (pinfunction "IO_L23N_3_M8") (pintype "bidirectional"))
    )
    (net (code "221") (name "unconnected-(U37D-IO_L23P_3-PadM7)") (class "Default")
      (node (ref "U37") (pin "M7") (pinfunction "IO_L23P_3_M7") (pintype "bidirectional"))
    )
    (net (code "222") (name "unconnected-(U37D-IO_L24N_3-PadP4)") (class "Default")
      (node (ref "U37") (pin "P4") (pinfunction "IO_L24N_3_P4") (pintype "bidirectional"))
    )
    (net (code "223") (name "unconnected-(U37D-IO_L24P_3-PadR4)") (class "Default")
      (node (ref "U37") (pin "R4") (pinfunction "IO_L24P_3_R4") (pintype "bidirectional"))
    )
    (net (code "224") (name "unconnected-(U37D-IO_L25N_3-PadL6)") (class "Default")
      (node (ref "U37") (pin "L6") (pinfunction "IO_L25N_3_L6") (pintype "bidirectional"))
    )
    (net (code "225") (name "unconnected-(U37D-IO_L25P_3-PadM6)") (class "Default")
      (node (ref "U37") (pin "M6") (pinfunction "IO_L25P_3_M6") (pintype "bidirectional"))
    )
    (net (code "226") (name "unconnected-(U37D-IO_L26N_3-PadN4)") (class "Default")
      (node (ref "U37") (pin "N4") (pinfunction "IO_L26N_3_N4") (pintype "bidirectional"))
    )
    (net (code "227") (name "unconnected-(U37D-IO_L26P_3-PadP3)") (class "Default")
      (node (ref "U37") (pin "P3") (pinfunction "IO_L26P_3_P3") (pintype "bidirectional"))
    )
    (net (code "228") (name "unconnected-(U37D-IO_L31N_VREF_3-PadM4)") (class "Default")
      (node (ref "U37") (pin "M4") (pinfunction "IO_L31N_VREF_3_M4") (pintype "bidirectional"))
    )
    (net (code "229") (name "unconnected-(U37D-IO_L31P_3-PadM5)") (class "Default")
      (node (ref "U37") (pin "M5") (pinfunction "IO_L31P_3_M5") (pintype "bidirectional"))
    )
    (net (code "230") (name "unconnected-(U37D-IO_L32N_M3DQ15_3-PadV1)") (class "Default")
      (node (ref "U37") (pin "V1") (pinfunction "IO_L32N_M3DQ15_3_V1") (pintype "bidirectional"))
    )
    (net (code "231") (name "unconnected-(U37D-IO_L32P_M3DQ14_3-PadV2)") (class "Default")
      (node (ref "U37") (pin "V2") (pinfunction "IO_L32P_M3DQ14_3_V2") (pintype "bidirectional"))
    )
    (net (code "232") (name "unconnected-(U37D-IO_L33N_M3DQ13_3-PadU1)") (class "Default")
      (node (ref "U37") (pin "U1") (pinfunction "IO_L33N_M3DQ13_3_U1") (pintype "bidirectional"))
    )
    (net (code "233") (name "unconnected-(U37D-IO_L33P_M3DQ12_3-PadU3)") (class "Default")
      (node (ref "U37") (pin "U3") (pinfunction "IO_L33P_M3DQ12_3_U3") (pintype "bidirectional"))
    )
    (net (code "234") (name "unconnected-(U37D-IO_L34N_M3UDQSN_3-PadT1)") (class "Default")
      (node (ref "U37") (pin "T1") (pinfunction "IO_L34N_M3UDQSN_3_T1") (pintype "bidirectional"))
    )
    (net (code "235") (name "unconnected-(U37D-IO_L34P_M3UDQS_3-PadT2)") (class "Default")
      (node (ref "U37") (pin "T2") (pinfunction "IO_L34P_M3UDQS_3_T2") (pintype "bidirectional"))
    )
    (net (code "236") (name "unconnected-(U37D-IO_L35N_M3DQ11_3-PadR1)") (class "Default")
      (node (ref "U37") (pin "R1") (pinfunction "IO_L35N_M3DQ11_3_R1") (pintype "bidirectional"))
    )
    (net (code "237") (name "unconnected-(U37D-IO_L35P_M3DQ10_3-PadR3)") (class "Default")
      (node (ref "U37") (pin "R3") (pinfunction "IO_L35P_M3DQ10_3_R3") (pintype "bidirectional"))
    )
    (net (code "238") (name "unconnected-(U37D-IO_L36N_M3DQ9_3-PadP1)") (class "Default")
      (node (ref "U37") (pin "P1") (pinfunction "IO_L36N_M3DQ9_3_P1") (pintype "bidirectional"))
    )
    (net (code "239") (name "unconnected-(U37D-IO_L36P_M3DQ8_3-PadP2)") (class "Default")
      (node (ref "U37") (pin "P2") (pinfunction "IO_L36P_M3DQ8_3_P2") (pintype "bidirectional"))
    )
    (net (code "240") (name "unconnected-(U37D-IO_L37N_M3DQ1_3-PadN1)") (class "Default")
      (node (ref "U37") (pin "N1") (pinfunction "IO_L37N_M3DQ1_3_N1") (pintype "bidirectional"))
    )
    (net (code "241") (name "unconnected-(U37D-IO_L37P_M3DQ0_3-PadN3)") (class "Default")
      (node (ref "U37") (pin "N3") (pinfunction "IO_L37P_M3DQ0_3_N3") (pintype "bidirectional"))
    )
    (net (code "242") (name "unconnected-(U37D-IO_L38N_M3DQ3_3-PadM1)") (class "Default")
      (node (ref "U37") (pin "M1") (pinfunction "IO_L38N_M3DQ3_3_M1") (pintype "bidirectional"))
    )
    (net (code "243") (name "unconnected-(U37D-IO_L38P_M3DQ2_3-PadM2)") (class "Default")
      (node (ref "U37") (pin "M2") (pinfunction "IO_L38P_M3DQ2_3_M2") (pintype "bidirectional"))
    )
    (net (code "244") (name "unconnected-(U37D-IO_L39N_M3LDQSN_3-PadL1)") (class "Default")
      (node (ref "U37") (pin "L1") (pinfunction "IO_L39N_M3LDQSN_3_L1") (pintype "bidirectional"))
    )
    (net (code "245") (name "unconnected-(U37D-IO_L39P_M3LDQS_3-PadL3)") (class "Default")
      (node (ref "U37") (pin "L3") (pinfunction "IO_L39P_M3LDQS_3_L3") (pintype "bidirectional"))
    )
    (net (code "246") (name "unconnected-(U37D-IO_L40N_M3DQ7_3-PadK1)") (class "Default")
      (node (ref "U37") (pin "K1") (pinfunction "IO_L40N_M3DQ7_3_K1") (pintype "bidirectional"))
    )
    (net (code "247") (name "unconnected-(U37D-IO_L40P_M3DQ6_3-PadK2)") (class "Default")
      (node (ref "U37") (pin "K2") (pinfunction "IO_L40P_M3DQ6_3_K2") (pintype "bidirectional"))
    )
    (net (code "248") (name "unconnected-(U37D-IO_L41N_GCLK26_M3DQ5_3-PadJ1)") (class "Default")
      (node (ref "U37") (pin "J1") (pinfunction "IO_L41N_GCLK26_M3DQ5_3_J1") (pintype "bidirectional"))
    )
    (net (code "249") (name "unconnected-(U37D-IO_L41P_GCLK27_M3DQ4_3-PadJ3)") (class "Default")
      (node (ref "U37") (pin "J3") (pinfunction "IO_L41P_GCLK27_M3DQ4_3_J3") (pintype "bidirectional"))
    )
    (net (code "250") (name "unconnected-(U37D-IO_L42N_GCLK24_M3LDM_3-PadL4)") (class "Default")
      (node (ref "U37") (pin "L4") (pinfunction "IO_L42N_GCLK24_M3LDM_3_L4") (pintype "bidirectional"))
    )
    (net (code "251") (name "unconnected-(U37D-IO_L42P_GCLK25_TRDY2_M3UDM_3-PadM3)") (class "Default")
      (node (ref "U37") (pin "M3") (pinfunction "IO_L42P_GCLK25_TRDY2_M3UDM_3_M3") (pintype "bidirectional"))
    )
    (net (code "252") (name "unconnected-(U37D-IO_L43N_GCLK22_IRDY2_M3CASN_3-PadK4)") (class "Default")
      (node (ref "U37") (pin "K4") (pinfunction "IO_L43N_GCLK22_IRDY2_M3CASN_3_K4") (pintype "bidirectional"))
    )
    (net (code "253") (name "unconnected-(U37D-IO_L43P_GCLK23_M3RASN_3-PadK5)") (class "Default")
      (node (ref "U37") (pin "K5") (pinfunction "IO_L43P_GCLK23_M3RASN_3_K5") (pintype "bidirectional"))
    )
    (net (code "254") (name "unconnected-(U37D-IO_L44N_GCLK20_M3A6_3-PadJ4)") (class "Default")
      (node (ref "U37") (pin "J4") (pinfunction "IO_L44N_GCLK20_M3A6_3_J4") (pintype "bidirectional"))
    )
    (net (code "255") (name "unconnected-(U37D-IO_L44P_GCLK21_M3A5_3-PadK3)") (class "Default")
      (node (ref "U37") (pin "K3") (pinfunction "IO_L44P_GCLK21_M3A5_3_K3") (pintype "bidirectional"))
    )
    (net (code "256") (name "unconnected-(U37D-IO_L45N_M3ODT_3-PadJ6)") (class "Default")
      (node (ref "U37") (pin "J6") (pinfunction "IO_L45N_M3ODT_3_J6") (pintype "bidirectional"))
    )
    (net (code "257") (name "unconnected-(U37D-IO_L45P_M3A3_3-PadK6)") (class "Default")
      (node (ref "U37") (pin "K6") (pinfunction "IO_L45P_M3A3_3_K6") (pintype "bidirectional"))
    )
    (net (code "258") (name "unconnected-(U37D-IO_L46N_M3CLKN_3-PadH3)") (class "Default")
      (node (ref "U37") (pin "H3") (pinfunction "IO_L46N_M3CLKN_3_H3") (pintype "bidirectional"))
    )
    (net (code "259") (name "unconnected-(U37D-IO_L46P_M3CLK_3-PadH4)") (class "Default")
      (node (ref "U37") (pin "H4") (pinfunction "IO_L46P_M3CLK_3_H4") (pintype "bidirectional"))
    )
    (net (code "260") (name "unconnected-(U37D-IO_L47N_M3A1_3-PadH1)") (class "Default")
      (node (ref "U37") (pin "H1") (pinfunction "IO_L47N_M3A1_3_H1") (pintype "bidirectional"))
    )
    (net (code "261") (name "unconnected-(U37D-IO_L47P_M3A0_3-PadH2)") (class "Default")
      (node (ref "U37") (pin "H2") (pinfunction "IO_L47P_M3A0_3_H2") (pintype "bidirectional"))
    )
    (net (code "262") (name "unconnected-(U37D-IO_L48N_M3BA1_3-PadG1)") (class "Default")
      (node (ref "U37") (pin "G1") (pinfunction "IO_L48N_M3BA1_3_G1") (pintype "bidirectional"))
    )
    (net (code "263") (name "unconnected-(U37D-IO_L48P_M3BA0_3-PadG3)") (class "Default")
      (node (ref "U37") (pin "G3") (pinfunction "IO_L48P_M3BA0_3_G3") (pintype "bidirectional"))
    )
    (net (code "264") (name "unconnected-(U37D-IO_L49N_M3A2_3-PadH5)") (class "Default")
      (node (ref "U37") (pin "H5") (pinfunction "IO_L49N_M3A2_3_H5") (pintype "bidirectional"))
    )
    (net (code "265") (name "unconnected-(U37D-IO_L49P_M3A7_3-PadH6)") (class "Default")
      (node (ref "U37") (pin "H6") (pinfunction "IO_L49P_M3A7_3_H6") (pintype "bidirectional"))
    )
    (net (code "266") (name "unconnected-(U37D-IO_L50N_M3BA2_3-PadF1)") (class "Default")
      (node (ref "U37") (pin "F1") (pinfunction "IO_L50N_M3BA2_3_F1") (pintype "bidirectional"))
    )
    (net (code "267") (name "unconnected-(U37D-IO_L50P_M3WE_3-PadF2)") (class "Default")
      (node (ref "U37") (pin "F2") (pinfunction "IO_L50P_M3WE_3_F2") (pintype "bidirectional"))
    )
    (net (code "268") (name "unconnected-(U37D-IO_L51N_M3A4_3-PadF3)") (class "Default")
      (node (ref "U37") (pin "F3") (pinfunction "IO_L51N_M3A4_3_F3") (pintype "bidirectional"))
    )
    (net (code "269") (name "unconnected-(U37D-IO_L51P_M3A10_3-PadG4)") (class "Default")
      (node (ref "U37") (pin "G4") (pinfunction "IO_L51P_M3A10_3_G4") (pintype "bidirectional"))
    )
    (net (code "270") (name "unconnected-(U37D-IO_L52N_M3A9_3-PadE1)") (class "Default")
      (node (ref "U37") (pin "E1") (pinfunction "IO_L52N_M3A9_3_E1") (pintype "bidirectional"))
    )
    (net (code "271") (name "unconnected-(U37D-IO_L52P_M3A8_3-PadE3)") (class "Default")
      (node (ref "U37") (pin "E3") (pinfunction "IO_L52P_M3A8_3_E3") (pintype "bidirectional"))
    )
    (net (code "272") (name "unconnected-(U37D-IO_L53N_M3A12_3-PadD1)") (class "Default")
      (node (ref "U37") (pin "D1") (pinfunction "IO_L53N_M3A12_3_D1") (pintype "bidirectional"))
    )
    (net (code "273") (name "unconnected-(U37D-IO_L53P_M3CKE_3-PadD2)") (class "Default")
      (node (ref "U37") (pin "D2") (pinfunction "IO_L53P_M3CKE_3_D2") (pintype "bidirectional"))
    )
    (net (code "274") (name "unconnected-(U37D-IO_L54N_M3A11_3-PadC1)") (class "Default")
      (node (ref "U37") (pin "C1") (pinfunction "IO_L54N_M3A11_3_C1") (pintype "bidirectional"))
    )
    (net (code "275") (name "unconnected-(U37D-IO_L54P_M3RESET_3-PadC3)") (class "Default")
      (node (ref "U37") (pin "C3") (pinfunction "IO_L54P_M3RESET_3_C3") (pintype "bidirectional"))
    )
    (net (code "276") (name "unconnected-(U37D-IO_L55N_M3A14_3-PadF5)") (class "Default")
      (node (ref "U37") (pin "F5") (pinfunction "IO_L55N_M3A14_3_F5") (pintype "bidirectional"))
    )
    (net (code "277") (name "unconnected-(U37D-IO_L55P_M3A13_3-PadG6)") (class "Default")
      (node (ref "U37") (pin "G6") (pinfunction "IO_L55P_M3A13_3_G6") (pintype "bidirectional"))
    )
    (net (code "278") (name "unconnected-(U37D-IO_L57N_VREF_3-PadK8)") (class "Default")
      (node (ref "U37") (pin "K8") (pinfunction "IO_L57N_VREF_3_K8") (pintype "bidirectional"))
    )
    (net (code "279") (name "unconnected-(U37D-IO_L57P_3-PadK7)") (class "Default")
      (node (ref "U37") (pin "K7") (pinfunction "IO_L57P_3_K7") (pintype "bidirectional"))
    )
    (net (code "280") (name "unconnected-(U37D-IO_L58N_3-PadE4)") (class "Default")
      (node (ref "U37") (pin "E4") (pinfunction "IO_L58N_3_E4") (pintype "bidirectional"))
    )
    (net (code "281") (name "unconnected-(U37D-IO_L58P_3-PadD5)") (class "Default")
      (node (ref "U37") (pin "D5") (pinfunction "IO_L58P_3_D5") (pintype "bidirectional"))
    )
    (net (code "282") (name "unconnected-(U37D-IO_L59N_3-PadH8)") (class "Default")
      (node (ref "U37") (pin "H8") (pinfunction "IO_L59N_3_H8") (pintype "bidirectional"))
    )
    (net (code "283") (name "unconnected-(U37D-IO_L59P_3-PadJ7)") (class "Default")
      (node (ref "U37") (pin "J7") (pinfunction "IO_L59P_3_J7") (pintype "bidirectional"))
    )
    (net (code "284") (name "unconnected-(U37D-IO_L60N_3-PadB1)") (class "Default")
      (node (ref "U37") (pin "B1") (pinfunction "IO_L60N_3_B1") (pintype "bidirectional"))
    )
    (net (code "285") (name "unconnected-(U37D-IO_L60P_3-PadB2)") (class "Default")
      (node (ref "U37") (pin "B2") (pinfunction "IO_L60P_3_B2") (pintype "bidirectional"))
    )
    (net (code "286") (name "unconnected-(U37D-IO_L80N_3-PadF7)") (class "Default")
      (node (ref "U37") (pin "F7") (pinfunction "IO_L80N_3_F7") (pintype "bidirectional"))
    )
    (net (code "287") (name "unconnected-(U37D-IO_L80P_3-PadG7)") (class "Default")
      (node (ref "U37") (pin "G7") (pinfunction "IO_L80P_3_G7") (pintype "bidirectional"))
    )
    (net (code "288") (name "unconnected-(U37D-IO_L81N_3-PadC4)") (class "Default")
      (node (ref "U37") (pin "C4") (pinfunction "IO_L81N_3_C4") (pintype "bidirectional"))
    )
    (net (code "289") (name "unconnected-(U37D-IO_L81P_3-PadD3)") (class "Default")
      (node (ref "U37") (pin "D3") (pinfunction "IO_L81P_3_D3") (pintype "bidirectional"))
    )
    (net (code "290") (name "unconnected-(U37D-IO_L82N_3-PadE6)") (class "Default")
      (node (ref "U37") (pin "E6") (pinfunction "IO_L82N_3_E6") (pintype "bidirectional"))
    )
    (net (code "291") (name "unconnected-(U37D-IO_L82P_3-PadE5)") (class "Default")
      (node (ref "U37") (pin "E5") (pinfunction "IO_L82P_3_E5") (pintype "bidirectional"))
    )
    (net (code "292") (name "unconnected-(U37D-IO_L83N_VREF_3-PadB3)") (class "Default")
      (node (ref "U37") (pin "B3") (pinfunction "IO_L83N_VREF_3_B3") (pintype "bidirectional"))
    )
    (net (code "293") (name "unconnected-(U37D-IO_L83P_3-PadA2)") (class "Default")
      (node (ref "U37") (pin "A2") (pinfunction "IO_L83P_3_A2") (pintype "bidirectional"))
    )
    (net (code "294") (name "unconnected-(U37E-CMPCS_B_2-PadY20)") (class "Default")
      (node (ref "U37") (pin "Y20") (pinfunction "CMPCS_B_2_Y20") (pintype "input+no_connect"))
    )
    (net (code "295") (name "unconnected-(U37H-NC-PadAB5)") (class "Default")
      (node (ref "U37") (pin "AB5") (pinfunction "NC_AB5") (pintype "passive"))
    )
    (net (code "296") (name "unconnected-(U37H-NC-PadE8)") (class "Default")
      (node (ref "U37") (pin "E8") (pinfunction "NC_E8") (pintype "passive"))
    )
    (net (code "297") (name "unconnected-(U37H-NC-PadE10)") (class "Default")
      (node (ref "U37") (pin "E10") (pinfunction "NC_E10") (pintype "passive"))
    )
    (net (code "298") (name "unconnected-(U37H-NC-PadF8)") (class "Default")
      (node (ref "U37") (pin "F8") (pinfunction "NC_F8") (pintype "passive"))
    )
    (net (code "299") (name "unconnected-(U37H-NC-PadF9)") (class "Default")
      (node (ref "U37") (pin "F9") (pinfunction "NC_F9") (pintype "passive"))
    )
    (net (code "300") (name "unconnected-(U37H-NC-PadF10)") (class "Default")
      (node (ref "U37") (pin "F10") (pinfunction "NC_F10") (pintype "passive"))
    )
    (net (code "301") (name "unconnected-(U37H-NC-PadF12)") (class "Default")
      (node (ref "U37") (pin "F12") (pinfunction "NC_F12") (pintype "passive"))
    )
    (net (code "302") (name "unconnected-(U37H-NC-PadG8)") (class "Default")
      (node (ref "U37") (pin "G8") (pinfunction "NC_G8") (pintype "passive"))
    )
    (net (code "303") (name "unconnected-(U37H-NC-PadG9)") (class "Default")
      (node (ref "U37") (pin "G9") (pinfunction "NC_G9") (pintype "passive"))
    )
    (net (code "304") (name "unconnected-(U37H-NC-PadG11)") (class "Default")
      (node (ref "U37") (pin "G11") (pinfunction "NC_G11") (pintype "passive"))
    )
    (net (code "305") (name "unconnected-(U37H-NC-PadH10)") (class "Default")
      (node (ref "U37") (pin "H10") (pinfunction "NC_H10") (pintype "passive"))
    )
    (net (code "306") (name "unconnected-(U37H-NC-PadH11)") (class "Default")
      (node (ref "U37") (pin "H11") (pinfunction "NC_H11") (pintype "passive"))
    )
    (net (code "307") (name "unconnected-(U37H-NC-PadH12)") (class "Default")
      (node (ref "U37") (pin "H12") (pinfunction "NC_H12") (pintype "passive"))
    )
    (net (code "308") (name "unconnected-(U37H-NC-PadR7)") (class "Default")
      (node (ref "U37") (pin "R7") (pinfunction "NC_R7") (pintype "passive"))
    )
    (net (code "309") (name "unconnected-(U37H-NC-PadR8)") (class "Default")
      (node (ref "U37") (pin "R8") (pinfunction "NC_R8") (pintype "passive"))
    )
    (net (code "310") (name "unconnected-(U37H-NC-PadR9)") (class "Default")
      (node (ref "U37") (pin "R9") (pinfunction "NC_R9") (pintype "passive"))
    )
    (net (code "311") (name "unconnected-(U37H-NC-PadR11)") (class "Default")
      (node (ref "U37") (pin "R11") (pinfunction "NC_R11") (pintype "passive"))
    )
    (net (code "312") (name "unconnected-(U37H-NC-PadR13)") (class "Default")
      (node (ref "U37") (pin "R13") (pinfunction "NC_R13") (pintype "passive"))
    )
    (net (code "313") (name "unconnected-(U37H-NC-PadR15)") (class "Default")
      (node (ref "U37") (pin "R15") (pinfunction "NC_R15") (pintype "passive"))
    )
    (net (code "314") (name "unconnected-(U37H-NC-PadR16)") (class "Default")
      (node (ref "U37") (pin "R16") (pinfunction "NC_R16") (pintype "passive"))
    )
    (net (code "315") (name "unconnected-(U37H-NC-PadT7)") (class "Default")
      (node (ref "U37") (pin "T7") (pinfunction "NC_T7") (pintype "passive"))
    )
    (net (code "316") (name "unconnected-(U37H-NC-PadT8)") (class "Default")
      (node (ref "U37") (pin "T8") (pinfunction "NC_T8") (pintype "passive"))
    )
    (net (code "317") (name "unconnected-(U37H-NC-PadT10)") (class "Default")
      (node (ref "U37") (pin "T10") (pinfunction "NC_T10") (pintype "passive"))
    )
    (net (code "318") (name "unconnected-(U37H-NC-PadT11)") (class "Default")
      (node (ref "U37") (pin "T11") (pinfunction "NC_T11") (pintype "passive"))
    )
    (net (code "319") (name "unconnected-(U37H-NC-PadT12)") (class "Default")
      (node (ref "U37") (pin "T12") (pinfunction "NC_T12") (pintype "passive"))
    )
    (net (code "320") (name "unconnected-(U37H-NC-PadT14)") (class "Default")
      (node (ref "U37") (pin "T14") (pinfunction "NC_T14") (pintype "passive"))
    )
    (net (code "321") (name "unconnected-(U37H-NC-PadT15)") (class "Default")
      (node (ref "U37") (pin "T15") (pinfunction "NC_T15") (pintype "passive"))
    )
    (net (code "322") (name "unconnected-(U37H-NC-PadT16)") (class "Default")
      (node (ref "U37") (pin "T16") (pinfunction "NC_T16") (pintype "passive"))
    )
    (net (code "323") (name "unconnected-(U37H-NC-PadU6)") (class "Default")
      (node (ref "U37") (pin "U6") (pinfunction "NC_U6") (pintype "passive"))
    )
    (net (code "324") (name "unconnected-(U37H-NC-PadU8)") (class "Default")
      (node (ref "U37") (pin "U8") (pinfunction "NC_U8") (pintype "passive"))
    )
    (net (code "325") (name "unconnected-(U37H-NC-PadU9)") (class "Default")
      (node (ref "U37") (pin "U9") (pinfunction "NC_U9") (pintype "passive"))
    )
    (net (code "326") (name "unconnected-(U37H-NC-PadU10)") (class "Default")
      (node (ref "U37") (pin "U10") (pinfunction "NC_U10") (pintype "passive"))
    )
    (net (code "327") (name "unconnected-(U37H-NC-PadU12)") (class "Default")
      (node (ref "U37") (pin "U12") (pinfunction "NC_U12") (pintype "passive"))
    )
    (net (code "328") (name "unconnected-(U37H-NC-PadU16)") (class "Default")
      (node (ref "U37") (pin "U16") (pinfunction "NC_U16") (pintype "passive"))
    )
    (net (code "329") (name "unconnected-(U37H-NC-PadU17)") (class "Default")
      (node (ref "U37") (pin "U17") (pinfunction "NC_U17") (pintype "passive"))
    )
    (net (code "330") (name "unconnected-(U37H-NC-PadV5)") (class "Default")
      (node (ref "U37") (pin "V5") (pinfunction "NC_V5") (pintype "passive"))
    )
    (net (code "331") (name "unconnected-(U37H-NC-PadV7)") (class "Default")
      (node (ref "U37") (pin "V7") (pinfunction "NC_V7") (pintype "passive"))
    )
    (net (code "332") (name "unconnected-(U37H-NC-PadV9)") (class "Default")
      (node (ref "U37") (pin "V9") (pinfunction "NC_V9") (pintype "passive"))
    )
    (net (code "333") (name "unconnected-(U37H-NC-PadV13)") (class "Default")
      (node (ref "U37") (pin "V13") (pinfunction "NC_V13") (pintype "passive"))
    )
    (net (code "334") (name "unconnected-(U37H-NC-PadV17)") (class "Default")
      (node (ref "U37") (pin "V17") (pinfunction "NC_V17") (pintype "passive"))
    )
    (net (code "335") (name "unconnected-(U37H-NC-PadV18)") (class "Default")
      (node (ref "U37") (pin "V18") (pinfunction "NC_V18") (pintype "passive"))
    )
    (net (code "336") (name "unconnected-(U37H-NC-PadV19)") (class "Default")
      (node (ref "U37") (pin "V19") (pinfunction "NC_V19") (pintype "passive"))
    )
    (net (code "337") (name "unconnected-(U37H-NC-PadW6)") (class "Default")
      (node (ref "U37") (pin "W6") (pinfunction "NC_W6") (pintype "passive"))
    )
    (net (code "338") (name "unconnected-(U37H-NC-PadW8)") (class "Default")
      (node (ref "U37") (pin "W8") (pinfunction "NC_W8") (pintype "passive"))
    )
    (net (code "339") (name "unconnected-(U37H-NC-PadW9)") (class "Default")
      (node (ref "U37") (pin "W9") (pinfunction "NC_W9") (pintype "passive"))
    )
    (net (code "340") (name "unconnected-(U37H-NC-PadW10)") (class "Default")
      (node (ref "U37") (pin "W10") (pinfunction "NC_W10") (pintype "passive"))
    )
    (net (code "341") (name "unconnected-(U37H-NC-PadW13)") (class "Default")
      (node (ref "U37") (pin "W13") (pinfunction "NC_W13") (pintype "passive"))
    )
    (net (code "342") (name "unconnected-(U37H-NC-PadW14)") (class "Default")
      (node (ref "U37") (pin "W14") (pinfunction "NC_W14") (pintype "passive"))
    )
    (net (code "343") (name "unconnected-(U37H-NC-PadW15)") (class "Default")
      (node (ref "U37") (pin "W15") (pinfunction "NC_W15") (pintype "passive"))
    )
    (net (code "344") (name "unconnected-(U37H-NC-PadW17)") (class "Default")
      (node (ref "U37") (pin "W17") (pinfunction "NC_W17") (pintype "passive"))
    )
    (net (code "345") (name "unconnected-(U37H-NC-PadW18)") (class "Default")
      (node (ref "U37") (pin "W18") (pinfunction "NC_W18") (pintype "passive"))
    )
    (net (code "346") (name "unconnected-(U37H-NC-PadY5)") (class "Default")
      (node (ref "U37") (pin "Y5") (pinfunction "NC_Y5") (pintype "passive"))
    )
    (net (code "347") (name "unconnected-(U37H-NC-PadY6)") (class "Default")
      (node (ref "U37") (pin "Y6") (pinfunction "NC_Y6") (pintype "passive"))
    )
    (net (code "348") (name "unconnected-(U37H-NC-PadY8)") (class "Default")
      (node (ref "U37") (pin "Y8") (pinfunction "NC_Y8") (pintype "passive"))
    )
    (net (code "349") (name "unconnected-(U37H-NC-PadY10)") (class "Default")
      (node (ref "U37") (pin "Y10") (pinfunction "NC_Y10") (pintype "passive"))
    )
    (net (code "350") (name "unconnected-(U37H-NC-PadY14)") (class "Default")
      (node (ref "U37") (pin "Y14") (pinfunction "NC_Y14") (pintype "passive"))
    )
    (net (code "351") (name "unconnected-(U37H-NC-PadY16)") (class "Default")
      (node (ref "U37") (pin "Y16") (pinfunction "NC_Y16") (pintype "passive"))
    )
    (net (code "352") (name "unconnected-(U37H-NC-PadY18)") (class "Default")
      (node (ref "U37") (pin "Y18") (pinfunction "NC_Y18") (pintype "passive"))
    )
  )
)
